# line_sensor.net
KiCad netlist of a schematic drawn in EAGLE
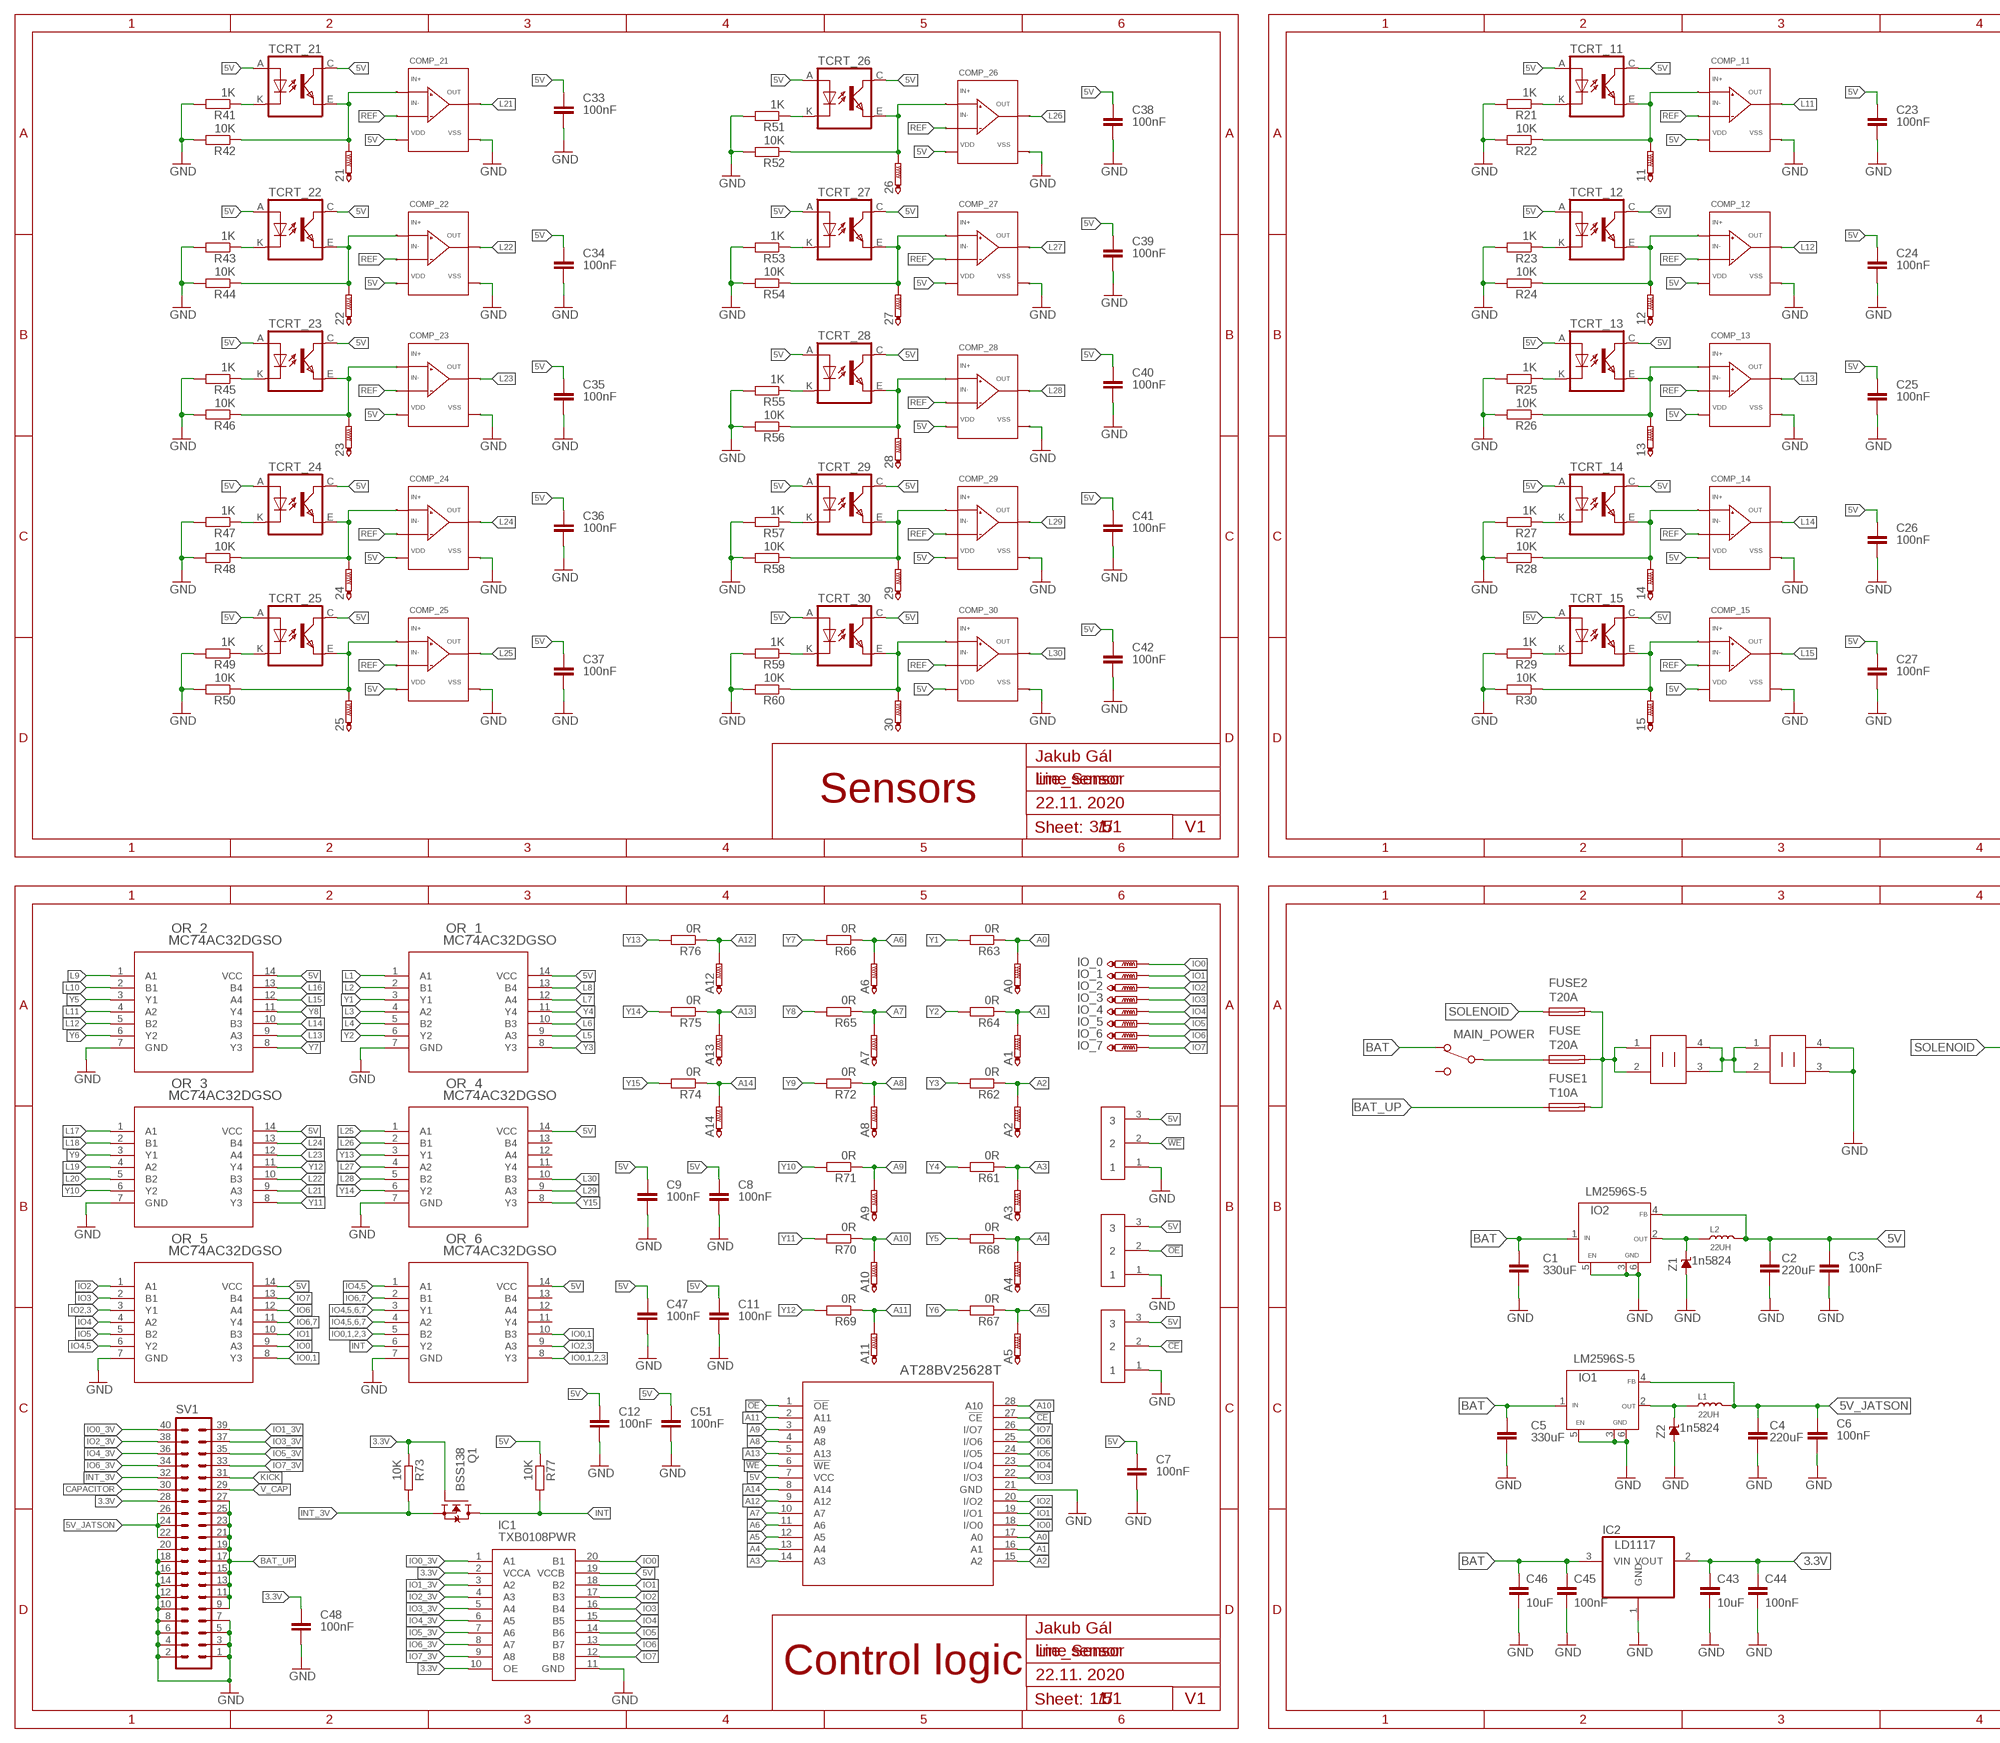
[diagram p0: schematic, sheet 1, part 1 of 2]
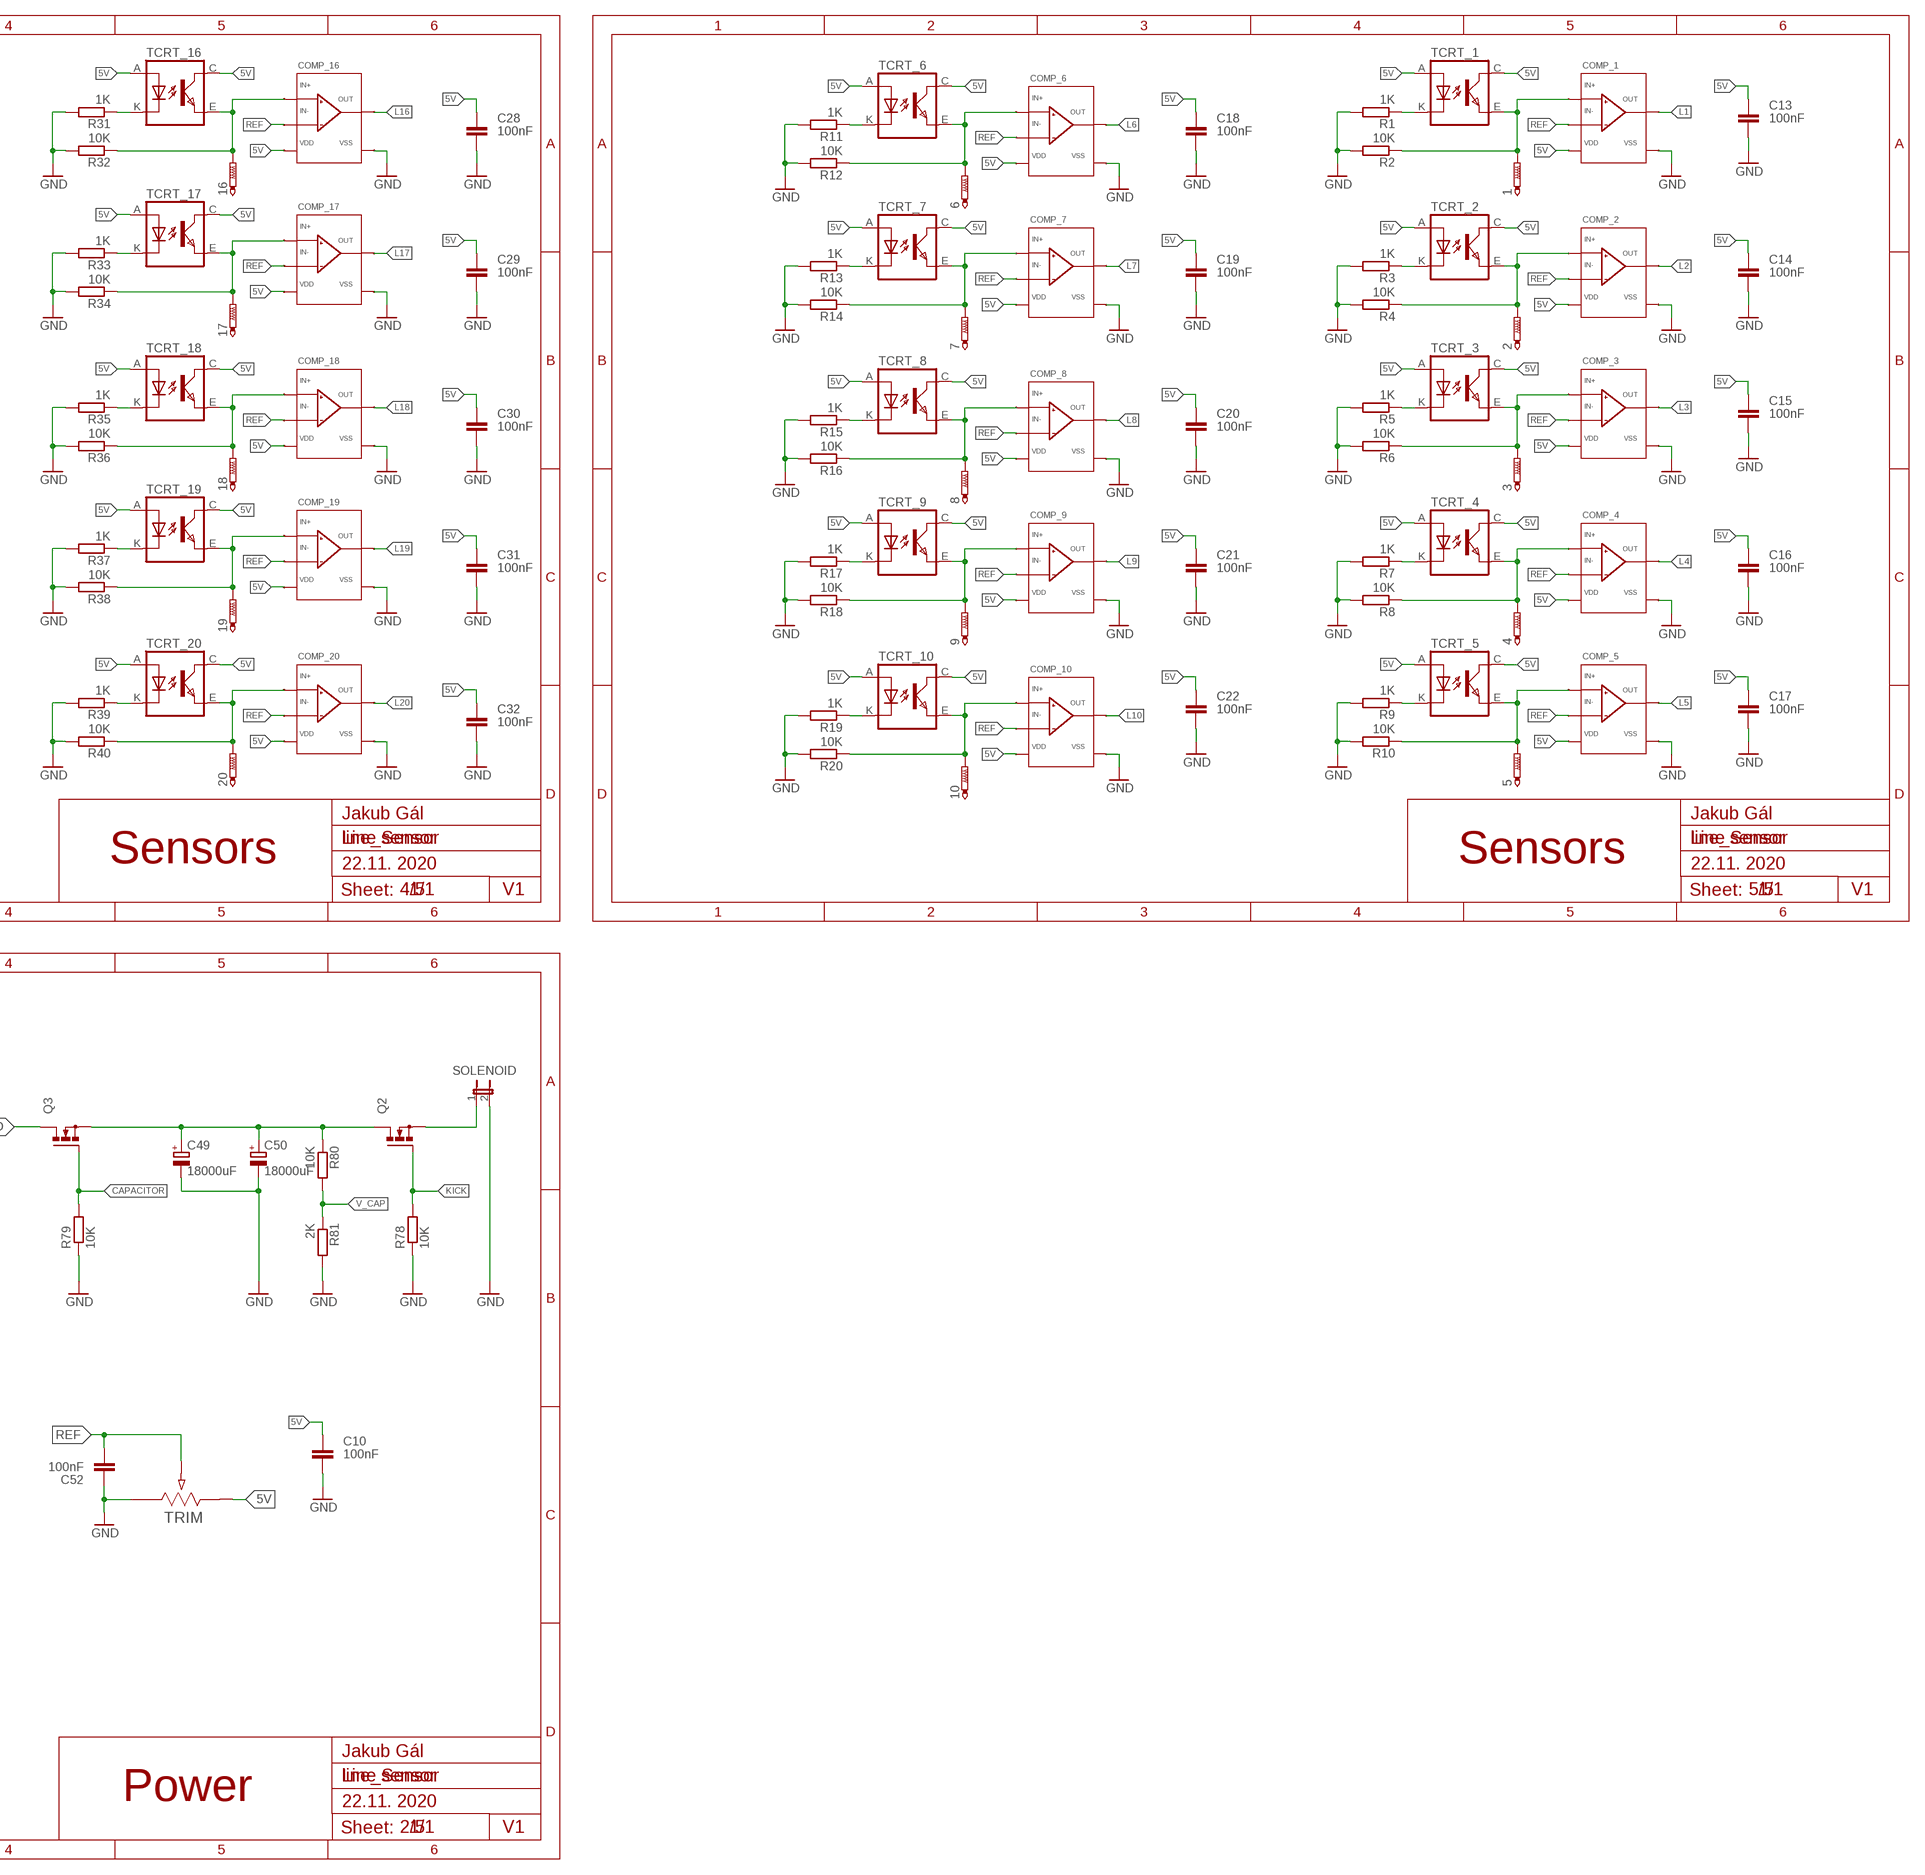
[diagram p1: schematic, sheet 1, part 2 of 2]

(export (version "E")
  (design (tool "Eeschema 10.0.6"))
  (components
    (comp (ref "!CE")
      (value "0603_S")
      (footprint "eagle-import:0603_S")
      (libsource (lib "eagle-import") (part "0603_S"))
    )
    (comp (ref "!OE")
      (value "0603_S")
      (footprint "eagle-import:0603_S")
      (libsource (lib "eagle-import") (part "0603_S"))
    )
    (comp (ref "!WE")
      (value "0603_S")
      (footprint "eagle-import:0603_S")
      (libsource (lib "eagle-import") (part "0603_S"))
    )
    (comp (ref "1")
      (value "PTR1TP20R")
      (footprint "eagle-import:TP20R")
      (libsource (lib "eagle-import") (part "PTR1TP20R"))
    )
    (comp (ref "2")
      (value "PTR1TP20R")
      (footprint "eagle-import:TP20R")
      (libsource (lib "eagle-import") (part "PTR1TP20R"))
    )
    (comp (ref "3")
      (value "PTR1TP20R")
      (footprint "eagle-import:TP20R")
      (libsource (lib "eagle-import") (part "PTR1TP20R"))
    )
    (comp (ref "4")
      (value "PTR1TP20R")
      (footprint "eagle-import:TP20R")
      (libsource (lib "eagle-import") (part "PTR1TP20R"))
    )
    (comp (ref "5")
      (value "PTR1TP20R")
      (footprint "eagle-import:TP20R")
      (libsource (lib "eagle-import") (part "PTR1TP20R"))
    )
    (comp (ref "6")
      (value "PTR1TP20R")
      (footprint "eagle-import:TP20R")
      (libsource (lib "eagle-import") (part "PTR1TP20R"))
    )
    (comp (ref "7")
      (value "PTR1TP20R")
      (footprint "eagle-import:TP20R")
      (libsource (lib "eagle-import") (part "PTR1TP20R"))
    )
    (comp (ref "8")
      (value "PTR1TP20R")
      (footprint "eagle-import:TP20R")
      (libsource (lib "eagle-import") (part "PTR1TP20R"))
    )
    (comp (ref "9")
      (value "PTR1TP20R")
      (footprint "eagle-import:TP20R")
      (libsource (lib "eagle-import") (part "PTR1TP20R"))
    )
    (comp (ref "10")
      (value "PTR1TP20R")
      (footprint "eagle-import:TP20R")
      (libsource (lib "eagle-import") (part "PTR1TP20R"))
    )
    (comp (ref "11")
      (value "PTR1TP20R")
      (footprint "eagle-import:TP20R")
      (libsource (lib "eagle-import") (part "PTR1TP20R"))
    )
    (comp (ref "12")
      (value "PTR1TP20R")
      (footprint "eagle-import:TP20R")
      (libsource (lib "eagle-import") (part "PTR1TP20R"))
    )
    (comp (ref "13")
      (value "PTR1TP20R")
      (footprint "eagle-import:TP20R")
      (libsource (lib "eagle-import") (part "PTR1TP20R"))
    )
    (comp (ref "14")
      (value "PTR1TP20R")
      (footprint "eagle-import:TP20R")
      (libsource (lib "eagle-import") (part "PTR1TP20R"))
    )
    (comp (ref "15")
      (value "PTR1TP20R")
      (footprint "eagle-import:TP20R")
      (libsource (lib "eagle-import") (part "PTR1TP20R"))
    )
    (comp (ref "16")
      (value "PTR1TP20R")
      (footprint "eagle-import:TP20R")
      (libsource (lib "eagle-import") (part "PTR1TP20R"))
    )
    (comp (ref "17")
      (value "PTR1TP20R")
      (footprint "eagle-import:TP20R")
      (libsource (lib "eagle-import") (part "PTR1TP20R"))
    )
    (comp (ref "18")
      (value "PTR1TP20R")
      (footprint "eagle-import:TP20R")
      (libsource (lib "eagle-import") (part "PTR1TP20R"))
    )
    (comp (ref "19")
      (value "PTR1TP20R")
      (footprint "eagle-import:TP20R")
      (libsource (lib "eagle-import") (part "PTR1TP20R"))
    )
    (comp (ref "20")
      (value "PTR1TP20R")
      (footprint "eagle-import:TP20R")
      (libsource (lib "eagle-import") (part "PTR1TP20R"))
    )
    (comp (ref "21")
      (value "PTR1TP20R")
      (footprint "eagle-import:TP20R")
      (libsource (lib "eagle-import") (part "PTR1TP20R"))
    )
    (comp (ref "22")
      (value "PTR1TP20R")
      (footprint "eagle-import:TP20R")
      (libsource (lib "eagle-import") (part "PTR1TP20R"))
    )
    (comp (ref "23")
      (value "PTR1TP20R")
      (footprint "eagle-import:TP20R")
      (libsource (lib "eagle-import") (part "PTR1TP20R"))
    )
    (comp (ref "24")
      (value "PTR1TP20R")
      (footprint "eagle-import:TP20R")
      (libsource (lib "eagle-import") (part "PTR1TP20R"))
    )
    (comp (ref "25")
      (value "PTR1TP20R")
      (footprint "eagle-import:TP20R")
      (libsource (lib "eagle-import") (part "PTR1TP20R"))
    )
    (comp (ref "26")
      (value "PTR1TP20R")
      (footprint "eagle-import:TP20R")
      (libsource (lib "eagle-import") (part "PTR1TP20R"))
    )
    (comp (ref "27")
      (value "PTR1TP20R")
      (footprint "eagle-import:TP20R")
      (libsource (lib "eagle-import") (part "PTR1TP20R"))
    )
    (comp (ref "28")
      (value "PTR1TP20R")
      (footprint "eagle-import:TP20R")
      (libsource (lib "eagle-import") (part "PTR1TP20R"))
    )
    (comp (ref "29")
      (value "PTR1TP20R")
      (footprint "eagle-import:TP20R")
      (libsource (lib "eagle-import") (part "PTR1TP20R"))
    )
    (comp (ref "30")
      (value "PTR1TP20R")
      (footprint "eagle-import:TP20R")
      (libsource (lib "eagle-import") (part "PTR1TP20R"))
    )
    (comp (ref "A0")
      (value "PTR1TP20R")
      (footprint "eagle-import:TP20R")
      (libsource (lib "eagle-import") (part "PTR1TP20R"))
    )
    (comp (ref "A1")
      (value "PTR1TP20R")
      (footprint "eagle-import:TP20R")
      (libsource (lib "eagle-import") (part "PTR1TP20R"))
    )
    (comp (ref "A2")
      (value "PTR1TP20R")
      (footprint "eagle-import:TP20R")
      (libsource (lib "eagle-import") (part "PTR1TP20R"))
    )
    (comp (ref "A3")
      (value "PTR1TP20R")
      (footprint "eagle-import:TP20R")
      (libsource (lib "eagle-import") (part "PTR1TP20R"))
    )
    (comp (ref "A4")
      (value "PTR1TP20R")
      (footprint "eagle-import:TP20R")
      (libsource (lib "eagle-import") (part "PTR1TP20R"))
    )
    (comp (ref "A5")
      (value "PTR1TP20R")
      (footprint "eagle-import:TP20R")
      (libsource (lib "eagle-import") (part "PTR1TP20R"))
    )
    (comp (ref "A6")
      (value "PTR1TP20R")
      (footprint "eagle-import:TP20R")
      (libsource (lib "eagle-import") (part "PTR1TP20R"))
    )
    (comp (ref "A7")
      (value "PTR1TP20R")
      (footprint "eagle-import:TP20R")
      (libsource (lib "eagle-import") (part "PTR1TP20R"))
    )
    (comp (ref "A8")
      (value "PTR1TP20R")
      (footprint "eagle-import:TP20R")
      (libsource (lib "eagle-import") (part "PTR1TP20R"))
    )
    (comp (ref "A9")
      (value "PTR1TP20R")
      (footprint "eagle-import:TP20R")
      (libsource (lib "eagle-import") (part "PTR1TP20R"))
    )
    (comp (ref "A10")
      (value "PTR1TP20R")
      (footprint "eagle-import:TP20R")
      (libsource (lib "eagle-import") (part "PTR1TP20R"))
    )
    (comp (ref "A11")
      (value "PTR1TP20R")
      (footprint "eagle-import:TP20R")
      (libsource (lib "eagle-import") (part "PTR1TP20R"))
    )
    (comp (ref "A12")
      (value "PTR1TP20R")
      (footprint "eagle-import:TP20R")
      (libsource (lib "eagle-import") (part "PTR1TP20R"))
    )
    (comp (ref "A13")
      (value "PTR1TP20R")
      (footprint "eagle-import:TP20R")
      (libsource (lib "eagle-import") (part "PTR1TP20R"))
    )
    (comp (ref "A14")
      (value "PTR1TP20R")
      (footprint "eagle-import:TP20R")
      (libsource (lib "eagle-import") (part "PTR1TP20R"))
    )
    (comp (ref "AT28BV25628T")
      (value "AT28BV25628T_ATM-M")
      (footprint "eagle-import:28T_ATM-M")
      (fields (field (name "MANUFACTURER_PART_NUMBER") "AT28BV256-20TU"))
      (libsource (lib "eagle-import") (part "AT28BV25628T_ATM-M"))
    )
    (comp (ref "C1")
      (value "330uF")
      (footprint "eagle-import:CAPM7343X310")
      (libsource (lib "eagle-import") (part "CTANTALUM-2917(7343-METRIC)_"))
    )
    (comp (ref "C2")
      (value "220uF")
      (footprint "eagle-import:CAPM7343X310")
      (libsource (lib "eagle-import") (part "CTANTALUM-2917(7343-METRIC)_"))
    )
    (comp (ref "C3")
      (value "100nF")
      (footprint "eagle-import:C0603")
      (libsource (lib "eagle-import") (part "C-EUC0603"))
    )
    (comp (ref "C4")
      (value "220uF")
      (footprint "eagle-import:CAPM7343X310")
      (libsource (lib "eagle-import") (part "CTANTALUM-2917(7343-METRIC)_"))
    )
    (comp (ref "C5")
      (value "330uF")
      (footprint "eagle-import:CAPM7343X310")
      (libsource (lib "eagle-import") (part "CTANTALUM-2917(7343-METRIC)_"))
    )
    (comp (ref "C6")
      (value "100nF")
      (footprint "eagle-import:C0603")
      (libsource (lib "eagle-import") (part "C-EUC0603"))
    )
    (comp (ref "C7")
      (value "100nF")
      (footprint "eagle-import:C0603")
      (libsource (lib "eagle-import") (part "C-EUC0603"))
    )
    (comp (ref "C8")
      (value "100nF")
      (footprint "eagle-import:C0603")
      (libsource (lib "eagle-import") (part "C-EUC0603"))
    )
    (comp (ref "C9")
      (value "100nF")
      (footprint "eagle-import:C0603")
      (libsource (lib "eagle-import") (part "C-EUC0603"))
    )
    (comp (ref "C10")
      (value "100nF")
      (footprint "eagle-import:C0603")
      (libsource (lib "eagle-import") (part "C-EUC0603"))
    )
    (comp (ref "C11")
      (value "100nF")
      (footprint "eagle-import:C0603")
      (libsource (lib "eagle-import") (part "C-EUC0603"))
    )
    (comp (ref "C12")
      (value "100nF")
      (footprint "eagle-import:C0603")
      (libsource (lib "eagle-import") (part "C-EUC0603"))
    )
    (comp (ref "C13")
      (value "100nF")
      (footprint "eagle-import:C0603")
      (libsource (lib "eagle-import") (part "C-EUC0603"))
    )
    (comp (ref "C14")
      (value "100nF")
      (footprint "eagle-import:C0603")
      (libsource (lib "eagle-import") (part "C-EUC0603"))
    )
    (comp (ref "C15")
      (value "100nF")
      (footprint "eagle-import:C0603")
      (libsource (lib "eagle-import") (part "C-EUC0603"))
    )
    (comp (ref "C16")
      (value "100nF")
      (footprint "eagle-import:C0603")
      (libsource (lib "eagle-import") (part "C-EUC0603"))
    )
    (comp (ref "C17")
      (value "100nF")
      (footprint "eagle-import:C0603")
      (libsource (lib "eagle-import") (part "C-EUC0603"))
    )
    (comp (ref "C18")
      (value "100nF")
      (footprint "eagle-import:C0603")
      (libsource (lib "eagle-import") (part "C-EUC0603"))
    )
    (comp (ref "C19")
      (value "100nF")
      (footprint "eagle-import:C0603")
      (libsource (lib "eagle-import") (part "C-EUC0603"))
    )
    (comp (ref "C20")
      (value "100nF")
      (footprint "eagle-import:C0603")
      (libsource (lib "eagle-import") (part "C-EUC0603"))
    )
    (comp (ref "C21")
      (value "100nF")
      (footprint "eagle-import:C0603")
      (libsource (lib "eagle-import") (part "C-EUC0603"))
    )
    (comp (ref "C22")
      (value "100nF")
      (footprint "eagle-import:C0603")
      (libsource (lib "eagle-import") (part "C-EUC0603"))
    )
    (comp (ref "C23")
      (value "100nF")
      (footprint "eagle-import:C0603")
      (libsource (lib "eagle-import") (part "C-EUC0603"))
    )
    (comp (ref "C24")
      (value "100nF")
      (footprint "eagle-import:C0603")
      (libsource (lib "eagle-import") (part "C-EUC0603"))
    )
    (comp (ref "C25")
      (value "100nF")
      (footprint "eagle-import:C0603")
      (libsource (lib "eagle-import") (part "C-EUC0603"))
    )
    (comp (ref "C26")
      (value "100nF")
      (footprint "eagle-import:C0603")
      (libsource (lib "eagle-import") (part "C-EUC0603"))
    )
    (comp (ref "C27")
      (value "100nF")
      (footprint "eagle-import:C0603")
      (libsource (lib "eagle-import") (part "C-EUC0603"))
    )
    (comp (ref "C28")
      (value "100nF")
      (footprint "eagle-import:C0603")
      (libsource (lib "eagle-import") (part "C-EUC0603"))
    )
    (comp (ref "C29")
      (value "100nF")
      (footprint "eagle-import:C0603")
      (libsource (lib "eagle-import") (part "C-EUC0603"))
    )
    (comp (ref "C30")
      (value "100nF")
      (footprint "eagle-import:C0603")
      (libsource (lib "eagle-import") (part "C-EUC0603"))
    )
    (comp (ref "C31")
      (value "100nF")
      (footprint "eagle-import:C0603")
      (libsource (lib "eagle-import") (part "C-EUC0603"))
    )
    (comp (ref "C32")
      (value "100nF")
      (footprint "eagle-import:C0603")
      (libsource (lib "eagle-import") (part "C-EUC0603"))
    )
    (comp (ref "C33")
      (value "100nF")
      (footprint "eagle-import:C0603")
      (libsource (lib "eagle-import") (part "C-EUC0603"))
    )
    (comp (ref "C34")
      (value "100nF")
      (footprint "eagle-import:C0603")
      (libsource (lib "eagle-import") (part "C-EUC0603"))
    )
    (comp (ref "C35")
      (value "100nF")
      (footprint "eagle-import:C0603")
      (libsource (lib "eagle-import") (part "C-EUC0603"))
    )
    (comp (ref "C36")
      (value "100nF")
      (footprint "eagle-import:C0603")
      (libsource (lib "eagle-import") (part "C-EUC0603"))
    )
    (comp (ref "C37")
      (value "100nF")
      (footprint "eagle-import:C0603")
      (libsource (lib "eagle-import") (part "C-EUC0603"))
    )
    (comp (ref "C38")
      (value "100nF")
      (footprint "eagle-import:C0603")
      (libsource (lib "eagle-import") (part "C-EUC0603"))
    )
    (comp (ref "C39")
      (value "100nF")
      (footprint "eagle-import:C0603")
      (libsource (lib "eagle-import") (part "C-EUC0603"))
    )
    (comp (ref "C40")
      (value "100nF")
      (footprint "eagle-import:C0603")
      (libsource (lib "eagle-import") (part "C-EUC0603"))
    )
    (comp (ref "C41")
      (value "100nF")
      (footprint "eagle-import:C0603")
      (libsource (lib "eagle-import") (part "C-EUC0603"))
    )
    (comp (ref "C42")
      (value "100nF")
      (footprint "eagle-import:C0603")
      (libsource (lib "eagle-import") (part "C-EUC0603"))
    )
    (comp (ref "C43")
      (value "10uF")
      (footprint "eagle-import:C0603")
      (libsource (lib "eagle-import") (part "C-EUC0603"))
    )
    (comp (ref "C44")
      (value "100nF")
      (footprint "eagle-import:C0603")
      (libsource (lib "eagle-import") (part "C-EUC0603"))
    )
    (comp (ref "C45")
      (value "100nF")
      (footprint "eagle-import:C0603")
      (libsource (lib "eagle-import") (part "C-EUC0603"))
    )
    (comp (ref "C46")
      (value "10uF")
      (footprint "eagle-import:C0603")
      (libsource (lib "eagle-import") (part "C-EUC0603"))
    )
    (comp (ref "C47")
      (value "100nF")
      (footprint "eagle-import:C0603")
      (libsource (lib "eagle-import") (part "C-EUC0603"))
    )
    (comp (ref "C48")
      (value "100nF")
      (footprint "eagle-import:C0603")
      (libsource (lib "eagle-import") (part "C-EUC0603"))
    )
    (comp (ref "C49")
      (value "18000uF")
      (footprint "eagle-import:EB30D")
      (libsource (lib "eagle-import") (part "CPOL-EUE10-30"))
    )
    (comp (ref "C50")
      (value "18000uF")
      (footprint "eagle-import:EB30D")
      (libsource (lib "eagle-import") (part "CPOL-EUE10-30"))
    )
    (comp (ref "C51")
      (value "100nF")
      (footprint "eagle-import:C0603")
      (libsource (lib "eagle-import") (part "C-EUC0603"))
    )
    (comp (ref "C52")
      (value "100nF")
      (footprint "eagle-import:C0603")
      (libsource (lib "eagle-import") (part "C-EUC0603"))
    )
    (comp (ref "COMP_1")
      (value "TC75S56FUTE85LF")
      (footprint "eagle-import:SOT-353___(USV)_TOS")
      (libsource (lib "eagle-import") (part "TC75S56FUTE85LF"))
    )
    (comp (ref "COMP_2")
      (value "TC75S56FUTE85LF")
      (footprint "eagle-import:SOT-353___(USV)_TOS")
      (libsource (lib "eagle-import") (part "TC75S56FUTE85LF"))
    )
    (comp (ref "COMP_3")
      (value "TC75S56FUTE85LF")
      (footprint "eagle-import:SOT-353___(USV)_TOS")
      (libsource (lib "eagle-import") (part "TC75S56FUTE85LF"))
    )
    (comp (ref "COMP_4")
      (value "TC75S56FUTE85LF")
      (footprint "eagle-import:SOT-353___(USV)_TOS")
      (libsource (lib "eagle-import") (part "TC75S56FUTE85LF"))
    )
    (comp (ref "COMP_5")
      (value "TC75S56FUTE85LF")
      (footprint "eagle-import:SOT-353___(USV)_TOS")
      (libsource (lib "eagle-import") (part "TC75S56FUTE85LF"))
    )
    (comp (ref "COMP_6")
      (value "TC75S56FUTE85LF")
      (footprint "eagle-import:SOT-353___(USV)_TOS")
      (libsource (lib "eagle-import") (part "TC75S56FUTE85LF"))
    )
    (comp (ref "COMP_7")
      (value "TC75S56FUTE85LF")
      (footprint "eagle-import:SOT-353___(USV)_TOS")
      (libsource (lib "eagle-import") (part "TC75S56FUTE85LF"))
    )
    (comp (ref "COMP_8")
      (value "TC75S56FUTE85LF")
      (footprint "eagle-import:SOT-353___(USV)_TOS")
      (libsource (lib "eagle-import") (part "TC75S56FUTE85LF"))
    )
    (comp (ref "COMP_9")
      (value "TC75S56FUTE85LF")
      (footprint "eagle-import:SOT-353___(USV)_TOS")
      (libsource (lib "eagle-import") (part "TC75S56FUTE85LF"))
    )
    (comp (ref "COMP_10")
      (value "TC75S56FUTE85LF")
      (footprint "eagle-import:SOT-353___(USV)_TOS")
      (libsource (lib "eagle-import") (part "TC75S56FUTE85LF"))
    )
    (comp (ref "COMP_11")
      (value "TC75S56FUTE85LF")
      (footprint "eagle-import:SOT-353___(USV)_TOS")
      (libsource (lib "eagle-import") (part "TC75S56FUTE85LF"))
    )
    (comp (ref "COMP_12")
      (value "TC75S56FUTE85LF")
      (footprint "eagle-import:SOT-353___(USV)_TOS")
      (libsource (lib "eagle-import") (part "TC75S56FUTE85LF"))
    )
    (comp (ref "COMP_13")
      (value "TC75S56FUTE85LF")
      (footprint "eagle-import:SOT-353___(USV)_TOS")
      (libsource (lib "eagle-import") (part "TC75S56FUTE85LF"))
    )
    (comp (ref "COMP_14")
      (value "TC75S56FUTE85LF")
      (footprint "eagle-import:SOT-353___(USV)_TOS")
      (libsource (lib "eagle-import") (part "TC75S56FUTE85LF"))
    )
    (comp (ref "COMP_15")
      (value "TC75S56FUTE85LF")
      (footprint "eagle-import:SOT-353___(USV)_TOS")
      (libsource (lib "eagle-import") (part "TC75S56FUTE85LF"))
    )
    (comp (ref "COMP_16")
      (value "TC75S56FUTE85LF")
      (footprint "eagle-import:SOT-353___(USV)_TOS")
      (libsource (lib "eagle-import") (part "TC75S56FUTE85LF"))
    )
    (comp (ref "COMP_17")
      (value "TC75S56FUTE85LF")
      (footprint "eagle-import:SOT-353___(USV)_TOS")
      (libsource (lib "eagle-import") (part "TC75S56FUTE85LF"))
    )
    (comp (ref "COMP_18")
      (value "TC75S56FUTE85LF")
      (footprint "eagle-import:SOT-353___(USV)_TOS")
      (libsource (lib "eagle-import") (part "TC75S56FUTE85LF"))
    )
    (comp (ref "COMP_19")
      (value "TC75S56FUTE85LF")
      (footprint "eagle-import:SOT-353___(USV)_TOS")
      (libsource (lib "eagle-import") (part "TC75S56FUTE85LF"))
    )
    (comp (ref "COMP_20")
      (value "TC75S56FUTE85LF")
      (footprint "eagle-import:SOT-353___(USV)_TOS")
      (libsource (lib "eagle-import") (part "TC75S56FUTE85LF"))
    )
    (comp (ref "COMP_21")
      (value "TC75S56FUTE85LF")
      (footprint "eagle-import:SOT-353___(USV)_TOS")
      (libsource (lib "eagle-import") (part "TC75S56FUTE85LF"))
    )
    (comp (ref "COMP_22")
      (value "TC75S56FUTE85LF")
      (footprint "eagle-import:SOT-353___(USV)_TOS")
      (libsource (lib "eagle-import") (part "TC75S56FUTE85LF"))
    )
    (comp (ref "COMP_23")
      (value "TC75S56FUTE85LF")
      (footprint "eagle-import:SOT-353___(USV)_TOS")
      (libsource (lib "eagle-import") (part "TC75S56FUTE85LF"))
    )
    (comp (ref "COMP_24")
      (value "TC75S56FUTE85LF")
      (footprint "eagle-import:SOT-353___(USV)_TOS")
      (libsource (lib "eagle-import") (part "TC75S56FUTE85LF"))
    )
    (comp (ref "COMP_25")
      (value "TC75S56FUTE85LF")
      (footprint "eagle-import:SOT-353___(USV)_TOS")
      (libsource (lib "eagle-import") (part "TC75S56FUTE85LF"))
    )
    (comp (ref "COMP_26")
      (value "TC75S56FUTE85LF")
      (footprint "eagle-import:SOT-353___(USV)_TOS")
      (libsource (lib "eagle-import") (part "TC75S56FUTE85LF"))
    )
    (comp (ref "COMP_27")
      (value "TC75S56FUTE85LF")
      (footprint "eagle-import:SOT-353___(USV)_TOS")
      (libsource (lib "eagle-import") (part "TC75S56FUTE85LF"))
    )
    (comp (ref "COMP_28")
      (value "TC75S56FUTE85LF")
      (footprint "eagle-import:SOT-353___(USV)_TOS")
      (libsource (lib "eagle-import") (part "TC75S56FUTE85LF"))
    )
    (comp (ref "COMP_29")
      (value "TC75S56FUTE85LF")
      (footprint "eagle-import:SOT-353___(USV)_TOS")
      (libsource (lib "eagle-import") (part "TC75S56FUTE85LF"))
    )
    (comp (ref "COMP_30")
      (value "TC75S56FUTE85LF")
      (footprint "eagle-import:SOT-353___(USV)_TOS")
      (libsource (lib "eagle-import") (part "TC75S56FUTE85LF"))
    )
    (comp (ref "FUSE")
      (value "T20A")
      (footprint "eagle-import:SH22,5A")
      (libsource (lib "eagle-import") (part "POISTKA2A"))
    )
    (comp (ref "FUSE1")
      (value "T10A")
      (footprint "eagle-import:SH22,5A")
      (libsource (lib "eagle-import") (part "POISTKA2A"))
    )
    (comp (ref "FUSE2")
      (value "T20A")
      (footprint "eagle-import:SH22,5A")
      (libsource (lib "eagle-import") (part "POISTKA2A"))
    )
    (comp (ref "IC1")
      (value "TXB0108PWR")
      (footprint "eagle-import:SOP65P640X120-20N")
      (fields (field (name "MOUSER_PART_NUMBER") "595-TXB0108PWR"))
      (libsource (lib "eagle-import") (part "TXB0108PWR"))
    )
    (comp (ref "IC2")
      (value "LD1117")
      (footprint "eagle-import:SOT223")
      (fields (field (name "MF") "TEXAS INSTRUMENTS") (field (name "MPN") "REG1117FAKTTT"))
      (libsource (lib "eagle-import") (part "LD1117"))
    )
    (comp (ref "IO1")
      (value "LM2596S-5")
      (footprint "eagle-import:TO263-5")
      (libsource (lib "eagle-import") (part "LM2596S"))
    )
    (comp (ref "IO2")
      (value "LM2596S-5")
      (footprint "eagle-import:TO263-5")
      (libsource (lib "eagle-import") (part "LM2596S"))
    )
    (comp (ref "IO_0")
      (value "PTR1TP20R")
      (footprint "eagle-import:TP20R")
      (libsource (lib "eagle-import") (part "PTR1TP20R"))
    )
    (comp (ref "IO_1")
      (value "PTR1TP20R")
      (footprint "eagle-import:TP20R")
      (libsource (lib "eagle-import") (part "PTR1TP20R"))
    )
    (comp (ref "IO_2")
      (value "PTR1TP20R")
      (footprint "eagle-import:TP20R")
      (libsource (lib "eagle-import") (part "PTR1TP20R"))
    )
    (comp (ref "IO_3")
      (value "PTR1TP20R")
      (footprint "eagle-import:TP20R")
      (libsource (lib "eagle-import") (part "PTR1TP20R"))
    )
    (comp (ref "IO_4")
      (value "PTR1TP20R")
      (footprint "eagle-import:TP20R")
      (libsource (lib "eagle-import") (part "PTR1TP20R"))
    )
    (comp (ref "IO_5")
      (value "PTR1TP20R")
      (footprint "eagle-import:TP20R")
      (libsource (lib "eagle-import") (part "PTR1TP20R"))
    )
    (comp (ref "IO_6")
      (value "PTR1TP20R")
      (footprint "eagle-import:TP20R")
      (libsource (lib "eagle-import") (part "PTR1TP20R"))
    )
    (comp (ref "IO_7")
      (value "PTR1TP20R")
      (footprint "eagle-import:TP20R")
      (libsource (lib "eagle-import") (part "PTR1TP20R"))
    )
    (comp (ref "L1")
      (value "22UH")
      (footprint "eagle-import:INDUCTOR_L0630")
      (libsource (lib "eagle-import") (part "INDUCTOR/FERRITE-BEAD0630"))
    )
    (comp (ref "L2")
      (value "22UH")
      (footprint "eagle-import:INDUCTOR_L0630")
      (libsource (lib "eagle-import") (part "INDUCTOR/FERRITE-BEAD0630"))
    )
    (comp (ref "MAIN_POWER")
      (value "PREP-1PB")
      (footprint "eagle-import:P-B069B")
      (libsource (lib "eagle-import") (part "PREP-1PB"))
    )
    (comp (ref "OR_1")
      (value "MC74AC32DGSO")
      (footprint "eagle-import:SOIC-14_NB_ONS-M")
      (fields
        (field (name "MANUFACTURER_PART_NUMBER") "MC74VHC32DR2G")
        (field (name "COPYRIGHT") "Copyright (C) 2016 Accelerated Designs. All rights reserved")
      )
      (libsource (lib "eagle-import") (part "MC74AC32DGSOIC-14_NB_ONS-M"))
    )
    (comp (ref "OR_2")
      (value "MC74AC32DGSO")
      (footprint "eagle-import:SOIC-14_NB_ONS-M")
      (fields
        (field (name "MANUFACTURER_PART_NUMBER") "MC74VHC32DR2G")
        (field (name "COPYRIGHT") "Copyright (C) 2016 Accelerated Designs. All rights reserved")
      )
      (libsource (lib "eagle-import") (part "MC74AC32DGSOIC-14_NB_ONS-M"))
    )
    (comp (ref "OR_3")
      (value "MC74AC32DGSO")
      (footprint "eagle-import:SOIC-14_NB_ONS-M")
      (fields
        (field (name "MANUFACTURER_PART_NUMBER") "MC74VHC32DR2G")
        (field (name "COPYRIGHT") "Copyright (C) 2016 Accelerated Designs. All rights reserved")
      )
      (libsource (lib "eagle-import") (part "MC74AC32DGSOIC-14_NB_ONS-M"))
    )
    (comp (ref "OR_4")
      (value "MC74AC32DGSO")
      (footprint "eagle-import:SOIC-14_NB_ONS-M")
      (fields
        (field (name "MANUFACTURER_PART_NUMBER") "MC74VHC32DR2G")
        (field (name "COPYRIGHT") "Copyright (C) 2016 Accelerated Designs. All rights reserved")
      )
      (libsource (lib "eagle-import") (part "MC74AC32DGSOIC-14_NB_ONS-M"))
    )
    (comp (ref "OR_5")
      (value "MC74AC32DGSO")
      (footprint "eagle-import:SOIC-14_NB_ONS-M")
      (fields
        (field (name "MANUFACTURER_PART_NUMBER") "MC74VHC32DR2G")
        (field (name "COPYRIGHT") "Copyright (C) 2016 Accelerated Designs. All rights reserved")
      )
      (libsource (lib "eagle-import") (part "MC74AC32DGSOIC-14_NB_ONS-M"))
    )
    (comp (ref "OR_6")
      (value "MC74AC32DGSO")
      (footprint "eagle-import:SOIC-14_NB_ONS-M")
      (fields
        (field (name "MANUFACTURER_PART_NUMBER") "MC74VHC32DR2G")
        (field (name "COPYRIGHT") "Copyright (C) 2016 Accelerated Designs. All rights reserved")
      )
      (libsource (lib "eagle-import") (part "MC74AC32DGSOIC-14_NB_ONS-M"))
    )
    (comp (ref "Q1")
      (value "BSS138")
      (footprint "eagle-import:SOT23")
      (fields (field (name "MF") "Fairchild"))
      (libsource (lib "eagle-import") (part "BSS138"))
    )
    (comp (ref "Q2")
      (value "PMOSFET_NTO220BV")
      (footprint "eagle-import:TO220BV")
      (libsource (lib "eagle-import") (part "PMOSFET_NTO220BV"))
    )
    (comp (ref "Q3")
      (value "PMOSFET_NTO220BV")
      (footprint "eagle-import:TO220BV")
      (libsource (lib "eagle-import") (part "PMOSFET_NTO220BV"))
    )
    (comp (ref "R1")
      (value "1K")
      (footprint "eagle-import:R0603")
      (libsource (lib "eagle-import") (part "R-EU_R0603"))
    )
    (comp (ref "R2")
      (value "10K")
      (footprint "eagle-import:R0603")
      (libsource (lib "eagle-import") (part "R-EU_R0603"))
    )
    (comp (ref "R3")
      (value "1K")
      (footprint "eagle-import:R0603")
      (libsource (lib "eagle-import") (part "R-EU_R0603"))
    )
    (comp (ref "R4")
      (value "10K")
      (footprint "eagle-import:R0603")
      (libsource (lib "eagle-import") (part "R-EU_R0603"))
    )
    (comp (ref "R5")
      (value "1K")
      (footprint "eagle-import:R0603")
      (libsource (lib "eagle-import") (part "R-EU_R0603"))
    )
    (comp (ref "R6")
      (value "10K")
      (footprint "eagle-import:R0603")
      (libsource (lib "eagle-import") (part "R-EU_R0603"))
    )
    (comp (ref "R7")
      (value "1K")
      (footprint "eagle-import:R0603")
      (libsource (lib "eagle-import") (part "R-EU_R0603"))
    )
    (comp (ref "R8")
      (value "10K")
      (footprint "eagle-import:R0603")
      (libsource (lib "eagle-import") (part "R-EU_R0603"))
    )
    (comp (ref "R9")
      (value "1K")
      (footprint "eagle-import:R0603")
      (libsource (lib "eagle-import") (part "R-EU_R0603"))
    )
    (comp (ref "R10")
      (value "10K")
      (footprint "eagle-import:R0603")
      (libsource (lib "eagle-import") (part "R-EU_R0603"))
    )
    (comp (ref "R11")
      (value "1K")
      (footprint "eagle-import:R0603")
      (libsource (lib "eagle-import") (part "R-EU_R0603"))
    )
    (comp (ref "R12")
      (value "10K")
      (footprint "eagle-import:R0603")
      (libsource (lib "eagle-import") (part "R-EU_R0603"))
    )
    (comp (ref "R13")
      (value "1K")
      (footprint "eagle-import:R0603")
      (libsource (lib "eagle-import") (part "R-EU_R0603"))
    )
    (comp (ref "R14")
      (value "10K")
      (footprint "eagle-import:R0603")
      (libsource (lib "eagle-import") (part "R-EU_R0603"))
    )
    (comp (ref "R15")
      (value "1K")
      (footprint "eagle-import:R0603")
      (libsource (lib "eagle-import") (part "R-EU_R0603"))
    )
    (comp (ref "R16")
      (value "10K")
      (footprint "eagle-import:R0603")
      (libsource (lib "eagle-import") (part "R-EU_R0603"))
    )
    (comp (ref "R17")
      (value "1K")
      (footprint "eagle-import:R0603")
      (libsource (lib "eagle-import") (part "R-EU_R0603"))
    )
    (comp (ref "R18")
      (value "10K")
      (footprint "eagle-import:R0603")
      (libsource (lib "eagle-import") (part "R-EU_R0603"))
    )
    (comp (ref "R19")
      (value "1K")
      (footprint "eagle-import:R0603")
      (libsource (lib "eagle-import") (part "R-EU_R0603"))
    )
    (comp (ref "R20")
      (value "10K")
      (footprint "eagle-import:R0603")
      (libsource (lib "eagle-import") (part "R-EU_R0603"))
    )
    (comp (ref "R21")
      (value "1K")
      (footprint "eagle-import:R0603")
      (libsource (lib "eagle-import") (part "R-EU_R0603"))
    )
    (comp (ref "R22")
      (value "10K")
      (footprint "eagle-import:R0603")
      (libsource (lib "eagle-import") (part "R-EU_R0603"))
    )
    (comp (ref "R23")
      (value "1K")
      (footprint "eagle-import:R0603")
      (libsource (lib "eagle-import") (part "R-EU_R0603"))
    )
    (comp (ref "R24")
      (value "10K")
      (footprint "eagle-import:R0603")
      (libsource (lib "eagle-import") (part "R-EU_R0603"))
    )
    (comp (ref "R25")
      (value "1K")
      (footprint "eagle-import:R0603")
      (libsource (lib "eagle-import") (part "R-EU_R0603"))
    )
    (comp (ref "R26")
      (value "10K")
      (footprint "eagle-import:R0603")
      (libsource (lib "eagle-import") (part "R-EU_R0603"))
    )
    (comp (ref "R27")
      (value "1K")
      (footprint "eagle-import:R0603")
      (libsource (lib "eagle-import") (part "R-EU_R0603"))
    )
    (comp (ref "R28")
      (value "10K")
      (footprint "eagle-import:R0603")
      (libsource (lib "eagle-import") (part "R-EU_R0603"))
    )
    (comp (ref "R29")
      (value "1K")
      (footprint "eagle-import:R0603")
      (libsource (lib "eagle-import") (part "R-EU_R0603"))
    )
    (comp (ref "R30")
      (value "10K")
      (footprint "eagle-import:R0603")
      (libsource (lib "eagle-import") (part "R-EU_R0603"))
    )
    (comp (ref "R31")
      (value "1K")
      (footprint "eagle-import:R0603")
      (libsource (lib "eagle-import") (part "R-EU_R0603"))
    )
    (comp (ref "R32")
      (value "10K")
      (footprint "eagle-import:R0603")
      (libsource (lib "eagle-import") (part "R-EU_R0603"))
    )
    (comp (ref "R33")
      (value "1K")
      (footprint "eagle-import:R0603")
      (libsource (lib "eagle-import") (part "R-EU_R0603"))
    )
    (comp (ref "R34")
      (value "10K")
      (footprint "eagle-import:R0603")
      (libsource (lib "eagle-import") (part "R-EU_R0603"))
    )
    (comp (ref "R35")
      (value "1K")
      (footprint "eagle-import:R0603")
      (libsource (lib "eagle-import") (part "R-EU_R0603"))
    )
    (comp (ref "R36")
      (value "10K")
      (footprint "eagle-import:R0603")
      (libsource (lib "eagle-import") (part "R-EU_R0603"))
    )
    (comp (ref "R37")
      (value "1K")
      (footprint "eagle-import:R0603")
      (libsource (lib "eagle-import") (part "R-EU_R0603"))
    )
    (comp (ref "R38")
      (value "10K")
      (footprint "eagle-import:R0603")
      (libsource (lib "eagle-import") (part "R-EU_R0603"))
    )
    (comp (ref "R39")
      (value "1K")
      (footprint "eagle-import:R0603")
      (libsource (lib "eagle-import") (part "R-EU_R0603"))
    )
    (comp (ref "R40")
      (value "10K")
      (footprint "eagle-import:R0603")
      (libsource (lib "eagle-import") (part "R-EU_R0603"))
    )
    (comp (ref "R41")
      (value "1K")
      (footprint "eagle-import:R0603")
      (libsource (lib "eagle-import") (part "R-EU_R0603"))
    )
    (comp (ref "R42")
      (value "10K")
      (footprint "eagle-import:R0603")
      (libsource (lib "eagle-import") (part "R-EU_R0603"))
    )
    (comp (ref "R43")
      (value "1K")
      (footprint "eagle-import:R0603")
      (libsource (lib "eagle-import") (part "R-EU_R0603"))
    )
    (comp (ref "R44")
      (value "10K")
      (footprint "eagle-import:R0603")
      (libsource (lib "eagle-import") (part "R-EU_R0603"))
    )
    (comp (ref "R45")
      (value "1K")
      (footprint "eagle-import:R0603")
      (libsource (lib "eagle-import") (part "R-EU_R0603"))
    )
    (comp (ref "R46")
      (value "10K")
      (footprint "eagle-import:R0603")
      (libsource (lib "eagle-import") (part "R-EU_R0603"))
    )
    (comp (ref "R47")
      (value "1K")
      (footprint "eagle-import:R0603")
      (libsource (lib "eagle-import") (part "R-EU_R0603"))
    )
    (comp (ref "R48")
      (value "10K")
      (footprint "eagle-import:R0603")
      (libsource (lib "eagle-import") (part "R-EU_R0603"))
    )
    (comp (ref "R49")
      (value "1K")
      (footprint "eagle-import:R0603")
      (libsource (lib "eagle-import") (part "R-EU_R0603"))
    )
    (comp (ref "R50")
      (value "10K")
      (footprint "eagle-import:R0603")
      (libsource (lib "eagle-import") (part "R-EU_R0603"))
    )
    (comp (ref "R51")
      (value "1K")
      (footprint "eagle-import:R0603")
      (libsource (lib "eagle-import") (part "R-EU_R0603"))
    )
    (comp (ref "R52")
      (value "10K")
      (footprint "eagle-import:R0603")
      (libsource (lib "eagle-import") (part "R-EU_R0603"))
    )
    (comp (ref "R53")
      (value "1K")
      (footprint "eagle-import:R0603")
      (libsource (lib "eagle-import") (part "R-EU_R0603"))
    )
    (comp (ref "R54")
      (value "10K")
      (footprint "eagle-import:R0603")
      (libsource (lib "eagle-import") (part "R-EU_R0603"))
    )
    (comp (ref "R55")
      (value "1K")
      (footprint "eagle-import:R0603")
      (libsource (lib "eagle-import") (part "R-EU_R0603"))
    )
    (comp (ref "R56")
      (value "10K")
      (footprint "eagle-import:R0603")
      (libsource (lib "eagle-import") (part "R-EU_R0603"))
    )
    (comp (ref "R57")
      (value "1K")
      (footprint "eagle-import:R0603")
      (libsource (lib "eagle-import") (part "R-EU_R0603"))
    )
    (comp (ref "R58")
      (value "10K")
      (footprint "eagle-import:R0603")
      (libsource (lib "eagle-import") (part "R-EU_R0603"))
    )
    (comp (ref "R59")
      (value "1K")
      (footprint "eagle-import:R0603")
      (libsource (lib "eagle-import") (part "R-EU_R0603"))
    )
    (comp (ref "R60")
      (value "10K")
      (footprint "eagle-import:R0603")
      (libsource (lib "eagle-import") (part "R-EU_R0603"))
    )
    (comp (ref "R61")
      (value "0R")
      (footprint "eagle-import:R0603")
      (libsource (lib "eagle-import") (part "R-EU_R0603"))
    )
    (comp (ref "R62")
      (value "0R")
      (footprint "eagle-import:R0603")
      (libsource (lib "eagle-import") (part "R-EU_R0603"))
    )
    (comp (ref "R63")
      (value "0R")
      (footprint "eagle-import:R0603")
      (libsource (lib "eagle-import") (part "R-EU_R0603"))
    )
    (comp (ref "R64")
      (value "0R")
      (footprint "eagle-import:R0603")
      (libsource (lib "eagle-import") (part "R-EU_R0603"))
    )
    (comp (ref "R65")
      (value "0R")
      (footprint "eagle-import:R0603")
      (libsource (lib "eagle-import") (part "R-EU_R0603"))
    )
    (comp (ref "R66")
      (value "0R")
      (footprint "eagle-import:R0603")
      (libsource (lib "eagle-import") (part "R-EU_R0603"))
    )
    (comp (ref "R67")
      (value "0R")
      (footprint "eagle-import:R0603")
      (libsource (lib "eagle-import") (part "R-EU_R0603"))
    )
    (comp (ref "R68")
      (value "0R")
      (footprint "eagle-import:R0603")
      (libsource (lib "eagle-import") (part "R-EU_R0603"))
    )
    (comp (ref "R69")
      (value "0R")
      (footprint "eagle-import:R0603")
      (libsource (lib "eagle-import") (part "R-EU_R0603"))
    )
    (comp (ref "R70")
      (value "0R")
      (footprint "eagle-import:R0603")
      (libsource (lib "eagle-import") (part "R-EU_R0603"))
    )
    (comp (ref "R71")
      (value "0R")
      (footprint "eagle-import:R0603")
      (libsource (lib "eagle-import") (part "R-EU_R0603"))
    )
    (comp (ref "R72")
      (value "0R")
      (footprint "eagle-import:R0603")
      (libsource (lib "eagle-import") (part "R-EU_R0603"))
    )
    (comp (ref "R73")
      (value "10K")
      (footprint "eagle-import:R0603")
      (libsource (lib "eagle-import") (part "R-EU_R0603"))
    )
    (comp (ref "R74")
      (value "0R")
      (footprint "eagle-import:R0603")
      (libsource (lib "eagle-import") (part "R-EU_R0603"))
    )
    (comp (ref "R75")
      (value "0R")
      (footprint "eagle-import:R0603")
      (libsource (lib "eagle-import") (part "R-EU_R0603"))
    )
    (comp (ref "R76")
      (value "0R")
      (footprint "eagle-import:R0603")
      (libsource (lib "eagle-import") (part "R-EU_R0603"))
    )
    (comp (ref "R77")
      (value "10K")
      (footprint "eagle-import:R0603")
      (libsource (lib "eagle-import") (part "R-EU_R0603"))
    )
    (comp (ref "R78")
      (value "10K")
      (footprint "eagle-import:R1206")
      (libsource (lib "eagle-import") (part "R-EU_R1206"))
    )
    (comp (ref "R79")
      (value "10K")
      (footprint "eagle-import:R1206")
      (libsource (lib "eagle-import") (part "R-EU_R1206"))
    )
    (comp (ref "R80")
      (value "10K")
      (footprint "eagle-import:R0603")
      (libsource (lib "eagle-import") (part "R-EU_R0603"))
    )
    (comp (ref "R81")
      (value "2K")
      (footprint "eagle-import:R0603")
      (libsource (lib "eagle-import") (part "R-EU_R0603"))
    )
    (comp (ref "SOLENOID")
      (value "JP1E")
      (footprint "eagle-import:JP1")
      (libsource (lib "eagle-import") (part "JP1E"))
    )
    (comp (ref "SV1")
      (value "MLW40")
      (footprint "eagle-import:ML40")
      (libsource (lib "eagle-import") (part "MLW40"))
    )
    (comp (ref "TCRT_1")
      (value "TCRT5000")
      (footprint "eagle-import:TCRT5000")
      (libsource (lib "eagle-import") (part "TCRT5000"))
    )
    (comp (ref "TCRT_2")
      (value "TCRT5000")
      (footprint "eagle-import:TCRT5000")
      (libsource (lib "eagle-import") (part "TCRT5000"))
    )
    (comp (ref "TCRT_3")
      (value "TCRT5000")
      (footprint "eagle-import:TCRT5000")
      (libsource (lib "eagle-import") (part "TCRT5000"))
    )
    (comp (ref "TCRT_4")
      (value "TCRT5000")
      (footprint "eagle-import:TCRT5000")
      (libsource (lib "eagle-import") (part "TCRT5000"))
    )
    (comp (ref "TCRT_5")
      (value "TCRT5000")
      (footprint "eagle-import:TCRT5000")
      (libsource (lib "eagle-import") (part "TCRT5000"))
    )
    (comp (ref "TCRT_6")
      (value "TCRT5000")
      (footprint "eagle-import:TCRT5000")
      (libsource (lib "eagle-import") (part "TCRT5000"))
    )
    (comp (ref "TCRT_7")
      (value "TCRT5000")
      (footprint "eagle-import:TCRT5000")
      (libsource (lib "eagle-import") (part "TCRT5000"))
    )
    (comp (ref "TCRT_8")
      (value "TCRT5000")
      (footprint "eagle-import:TCRT5000")
      (libsource (lib "eagle-import") (part "TCRT5000"))
    )
    (comp (ref "TCRT_9")
      (value "TCRT5000")
      (footprint "eagle-import:TCRT5000")
      (libsource (lib "eagle-import") (part "TCRT5000"))
    )
    (comp (ref "TCRT_10")
      (value "TCRT5000")
      (footprint "eagle-import:TCRT5000")
      (libsource (lib "eagle-import") (part "TCRT5000"))
    )
    (comp (ref "TCRT_11")
      (value "TCRT5000")
      (footprint "eagle-import:TCRT5000")
      (libsource (lib "eagle-import") (part "TCRT5000"))
    )
    (comp (ref "TCRT_12")
      (value "TCRT5000")
      (footprint "eagle-import:TCRT5000")
      (libsource (lib "eagle-import") (part "TCRT5000"))
    )
    (comp (ref "TCRT_13")
      (value "TCRT5000")
      (footprint "eagle-import:TCRT5000")
      (libsource (lib "eagle-import") (part "TCRT5000"))
    )
    (comp (ref "TCRT_14")
      (value "TCRT5000")
      (footprint "eagle-import:TCRT5000")
      (libsource (lib "eagle-import") (part "TCRT5000"))
    )
    (comp (ref "TCRT_15")
      (value "TCRT5000")
      (footprint "eagle-import:TCRT5000")
      (libsource (lib "eagle-import") (part "TCRT5000"))
    )
    (comp (ref "TCRT_16")
      (value "TCRT5000")
      (footprint "eagle-import:TCRT5000")
      (libsource (lib "eagle-import") (part "TCRT5000"))
    )
    (comp (ref "TCRT_17")
      (value "TCRT5000")
      (footprint "eagle-import:TCRT5000")
      (libsource (lib "eagle-import") (part "TCRT5000"))
    )
    (comp (ref "TCRT_18")
      (value "TCRT5000")
      (footprint "eagle-import:TCRT5000")
      (libsource (lib "eagle-import") (part "TCRT5000"))
    )
    (comp (ref "TCRT_19")
      (value "TCRT5000")
      (footprint "eagle-import:TCRT5000")
      (libsource (lib "eagle-import") (part "TCRT5000"))
    )
    (comp (ref "TCRT_20")
      (value "TCRT5000")
      (footprint "eagle-import:TCRT5000")
      (libsource (lib "eagle-import") (part "TCRT5000"))
    )
    (comp (ref "TCRT_21")
      (value "TCRT5000")
      (footprint "eagle-import:TCRT5000")
      (libsource (lib "eagle-import") (part "TCRT5000"))
    )
    (comp (ref "TCRT_22")
      (value "TCRT5000")
      (footprint "eagle-import:TCRT5000")
      (libsource (lib "eagle-import") (part "TCRT5000"))
    )
    (comp (ref "TCRT_23")
      (value "TCRT5000")
      (footprint "eagle-import:TCRT5000")
      (libsource (lib "eagle-import") (part "TCRT5000"))
    )
    (comp (ref "TCRT_24")
      (value "TCRT5000")
      (footprint "eagle-import:TCRT5000")
      (libsource (lib "eagle-import") (part "TCRT5000"))
    )
    (comp (ref "TCRT_25")
      (value "TCRT5000")
      (footprint "eagle-import:TCRT5000")
      (libsource (lib "eagle-import") (part "TCRT5000"))
    )
    (comp (ref "TCRT_26")
      (value "TCRT5000")
      (footprint "eagle-import:TCRT5000")
      (libsource (lib "eagle-import") (part "TCRT5000"))
    )
    (comp (ref "TCRT_27")
      (value "TCRT5000")
      (footprint "eagle-import:TCRT5000")
      (libsource (lib "eagle-import") (part "TCRT5000"))
    )
    (comp (ref "TCRT_28")
      (value "TCRT5000")
      (footprint "eagle-import:TCRT5000")
      (libsource (lib "eagle-import") (part "TCRT5000"))
    )
    (comp (ref "TCRT_29")
      (value "TCRT5000")
      (footprint "eagle-import:TCRT5000")
      (libsource (lib "eagle-import") (part "TCRT5000"))
    )
    (comp (ref "TCRT_30")
      (value "TCRT5000")
      (footprint "eagle-import:TCRT5000")
      (libsource (lib "eagle-import") (part "TCRT5000"))
    )
    (comp (ref "TRIM")
      (value "3362W-1-103LF")
      (footprint "eagle-import:POT_3362W")
      (libsource (lib "eagle-import") (part "3362W-1-103LF"))
    )
    (comp (ref "U$4")
      (value "TERMINAL")
      (footprint "eagle-import:TERMINAL")
      (libsource (lib "eagle-import") (part "TERMINAL"))
    )
    (comp (ref "U$5")
      (value "TERMINAL")
      (footprint "eagle-import:TERMINAL")
      (libsource (lib "eagle-import") (part "TERMINAL"))
    )
    (comp (ref "Z1")
      (value "1n5824")
      (footprint "eagle-import:SUPRESSOR_SMAJ")
      (libsource (lib "eagle-import") (part "SUPRESSOR_TVS-UD-SMAJ"))
    )
    (comp (ref "Z2")
      (value "1n5824")
      (footprint "eagle-import:SUPRESSOR_SMAJ")
      (libsource (lib "eagle-import") (part "SUPRESSOR_TVS-UD-SMAJ"))
    )
  )
  (nets
    (net (code "1") (name "/~{CE}") (class "Default")
      (node (ref "!CE") (pin "2") (pinfunction "A2_2") (pintype "bidirectional"))
      (node (ref "AT28BV25628T") (pin "27") (pinfunction "~{CE}_27") (pintype "passive"))
    )
    (net (code "2") (name "/~{OE}") (class "Default")
      (node (ref "!OE") (pin "2") (pinfunction "A2_2") (pintype "bidirectional"))
      (node (ref "AT28BV25628T") (pin "1") (pinfunction "~{OE}_1") (pintype "output"))
    )
    (net (code "3") (name "/~{WE}") (class "Default")
      (node (ref "!WE") (pin "2") (pinfunction "A2_2") (pintype "bidirectional"))
      (node (ref "AT28BV25628T") (pin "6") (pinfunction "~{WE}_6") (pintype "passive"))
    )
    (net (code "4") (name "3.3V") (class "Default")
      (node (ref "C43") (pin "1") (pinfunction "1_1") (pintype "passive"))
      (node (ref "C44") (pin "1") (pinfunction "1_1") (pintype "passive"))
      (node (ref "C48") (pin "1") (pinfunction "1_1") (pintype "passive"))
      (node (ref "IC1") (pin "10") (pinfunction "OE_10") (pintype "bidirectional"))
      (node (ref "IC1") (pin "2") (pinfunction "VCCA_2") (pintype "bidirectional"))
      (node (ref "IC2") (pin "2") (pinfunction "VOUT_2") (pintype "output"))
      (node (ref "Q1") (pin "1") (pinfunction "G_1") (pintype "passive"))
      (node (ref "R73") (pin "1") (pinfunction "1_1") (pintype "passive"))
      (node (ref "SV1") (pin "28") (pinfunction "28_28") (pintype "passive"))
    )
    (net (code "5") (name "5V") (class "Default")
      (node (ref "!CE") (pin "3") (pinfunction "A3_3") (pintype "bidirectional"))
      (node (ref "!OE") (pin "3") (pinfunction "A3_3") (pintype "bidirectional"))
      (node (ref "!WE") (pin "3") (pinfunction "A3_3") (pintype "bidirectional"))
      (node (ref "AT28BV25628T") (pin "7") (pinfunction "VCC_7") (pintype "power_in"))
      (node (ref "C10") (pin "1") (pinfunction "1_1") (pintype "passive"))
      (node (ref "C11") (pin "1") (pinfunction "1_1") (pintype "passive"))
      (node (ref "C12") (pin "1") (pinfunction "1_1") (pintype "passive"))
      (node (ref "C13") (pin "1") (pinfunction "1_1") (pintype "passive"))
      (node (ref "C14") (pin "1") (pinfunction "1_1") (pintype "passive"))
      (node (ref "C15") (pin "1") (pinfunction "1_1") (pintype "passive"))
      (node (ref "C16") (pin "1") (pinfunction "1_1") (pintype "passive"))
      (node (ref "C17") (pin "1") (pinfunction "1_1") (pintype "passive"))
      (node (ref "C18") (pin "1") (pinfunction "1_1") (pintype "passive"))
      (node (ref "C19") (pin "1") (pinfunction "1_1") (pintype "passive"))
      (node (ref "C2") (pin "1") (pinfunction "1_1") (pintype "passive"))
      (node (ref "C20") (pin "1") (pinfunction "1_1") (pintype "passive"))
      (node (ref "C21") (pin "1") (pinfunction "1_1") (pintype "passive"))
      (node (ref "C22") (pin "1") (pinfunction "1_1") (pintype "passive"))
      (node (ref "C23") (pin "1") (pinfunction "1_1") (pintype "passive"))
      (node (ref "C24") (pin "1") (pinfunction "1_1") (pintype "passive"))
      (node (ref "C25") (pin "1") (pinfunction "1_1") (pintype "passive"))
      (node (ref "C26") (pin "1") (pinfunction "1_1") (pintype "passive"))
      (node (ref "C27") (pin "1") (pinfunction "1_1") (pintype "passive"))
      (node (ref "C28") (pin "1") (pinfunction "1_1") (pintype "passive"))
      (node (ref "C29") (pin "1") (pinfunction "1_1") (pintype "passive"))
      (node (ref "C3") (pin "1") (pinfunction "1_1") (pintype "passive"))
      (node (ref "C30") (pin "1") (pinfunction "1_1") (pintype "passive"))
      (node (ref "C31") (pin "1") (pinfunction "1_1") (pintype "passive"))
      (node (ref "C32") (pin "1") (pinfunction "1_1") (pintype "passive"))
      (node (ref "C33") (pin "1") (pinfunction "1_1") (pintype "passive"))
      (node (ref "C34") (pin "1") (pinfunction "1_1") (pintype "passive"))
      (node (ref "C35") (pin "1") (pinfunction "1_1") (pintype "passive"))
      (node (ref "C36") (pin "1") (pinfunction "1_1") (pintype "passive"))
      (node (ref "C37") (pin "1") (pinfunction "1_1") (pintype "passive"))
      (node (ref "C38") (pin "1") (pinfunction "1_1") (pintype "passive"))
      (node (ref "C39") (pin "1") (pinfunction "1_1") (pintype "passive"))
      (node (ref "C40") (pin "1") (pinfunction "1_1") (pintype "passive"))
      (node (ref "C41") (pin "1") (pinfunction "1_1") (pintype "passive"))
      (node (ref "C42") (pin "1") (pinfunction "1_1") (pintype "passive"))
      (node (ref "C47") (pin "1") (pinfunction "1_1") (pintype "passive"))
      (node (ref "C51") (pin "1") (pinfunction "1_1") (pintype "passive"))
      (node (ref "C7") (pin "1") (pinfunction "1_1") (pintype "passive"))
      (node (ref "C8") (pin "1") (pinfunction "1_1") (pintype "passive"))
      (node (ref "C9") (pin "1") (pinfunction "1_1") (pintype "passive"))
      (node (ref "COMP_1") (pin "5") (pinfunction "5_5") (pintype "passive"))
      (node (ref "COMP_10") (pin "5") (pinfunction "5_5") (pintype "passive"))
      (node (ref "COMP_11") (pin "5") (pinfunction "5_5") (pintype "passive"))
      (node (ref "COMP_12") (pin "5") (pinfunction "5_5") (pintype "passive"))
      (node (ref "COMP_13") (pin "5") (pinfunction "5_5") (pintype "passive"))
      (node (ref "COMP_14") (pin "5") (pinfunction "5_5") (pintype "passive"))
      (node (ref "COMP_15") (pin "5") (pinfunction "5_5") (pintype "passive"))
      (node (ref "COMP_16") (pin "5") (pinfunction "5_5") (pintype "passive"))
      (node (ref "COMP_17") (pin "5") (pinfunction "5_5") (pintype "passive"))
      (node (ref "COMP_18") (pin "5") (pinfunction "5_5") (pintype "passive"))
      (node (ref "COMP_19") (pin "5") (pinfunction "5_5") (pintype "passive"))
      (node (ref "COMP_2") (pin "5") (pinfunction "5_5") (pintype "passive"))
      (node (ref "COMP_20") (pin "5") (pinfunction "5_5") (pintype "passive"))
      (node (ref "COMP_21") (pin "5") (pinfunction "5_5") (pintype "passive"))
      (node (ref "COMP_22") (pin "5") (pinfunction "5_5") (pintype "passive"))
      (node (ref "COMP_23") (pin "5") (pinfunction "5_5") (pintype "passive"))
      (node (ref "COMP_24") (pin "5") (pinfunction "5_5") (pintype "passive"))
      (node (ref "COMP_25") (pin "5") (pinfunction "5_5") (pintype "passive"))
      (node (ref "COMP_26") (pin "5") (pinfunction "5_5") (pintype "passive"))
      (node (ref "COMP_27") (pin "5") (pinfunction "5_5") (pintype "passive"))
      (node (ref "COMP_28") (pin "5") (pinfunction "5_5") (pintype "passive"))
      (node (ref "COMP_29") (pin "5") (pinfunction "5_5") (pintype "passive"))
      (node (ref "COMP_3") (pin "5") (pinfunction "5_5") (pintype "passive"))
      (node (ref "COMP_30") (pin "5") (pinfunction "5_5") (pintype "passive"))
      (node (ref "COMP_4") (pin "5") (pinfunction "5_5") (pintype "passive"))
      (node (ref "COMP_5") (pin "5") (pinfunction "5_5") (pintype "passive"))
      (node (ref "COMP_6") (pin "5") (pinfunction "5_5") (pintype "passive"))
      (node (ref "COMP_7") (pin "5") (pinfunction "5_5") (pintype "passive"))
      (node (ref "COMP_8") (pin "5") (pinfunction "5_5") (pintype "passive"))
      (node (ref "COMP_9") (pin "5") (pinfunction "5_5") (pintype "passive"))
      (node (ref "IC1") (pin "19") (pinfunction "VCCB_19") (pintype "bidirectional"))
      (node (ref "IO2") (pin "4") (pinfunction "FB_4") (pintype "input"))
      (node (ref "L2") (pin "2") (pinfunction "2_2") (pintype "passive"))
      (node (ref "OR_1") (pin "14") (pinfunction "VCC_14") (pintype "power_in"))
      (node (ref "OR_2") (pin "14") (pinfunction "VCC_14") (pintype "power_in"))
      (node (ref "OR_3") (pin "14") (pinfunction "VCC_14") (pintype "power_in"))
      (node (ref "OR_4") (pin "14") (pinfunction "VCC_14") (pintype "power_in"))
      (node (ref "OR_5") (pin "14") (pinfunction "VCC_14") (pintype "power_in"))
      (node (ref "OR_6") (pin "14") (pinfunction "VCC_14") (pintype "power_in"))
      (node (ref "R77") (pin "1") (pinfunction "1_1") (pintype "passive"))
      (node (ref "TCRT_1") (pin "A") (pinfunction "ANODE_A") (pintype "passive"))
      (node (ref "TCRT_1") (pin "C") (pinfunction "COLLECTOR_C") (pintype "passive"))
      (node (ref "TCRT_10") (pin "A") (pinfunction "ANODE_A") (pintype "passive"))
      (node (ref "TCRT_10") (pin "C") (pinfunction "COLLECTOR_C") (pintype "passive"))
      (node (ref "TCRT_11") (pin "A") (pinfunction "ANODE_A") (pintype "passive"))
      (node (ref "TCRT_11") (pin "C") (pinfunction "COLLECTOR_C") (pintype "passive"))
      (node (ref "TCRT_12") (pin "A") (pinfunction "ANODE_A") (pintype "passive"))
      (node (ref "TCRT_12") (pin "C") (pinfunction "COLLECTOR_C") (pintype "passive"))
      (node (ref "TCRT_13") (pin "A") (pinfunction "ANODE_A") (pintype "passive"))
      (node (ref "TCRT_13") (pin "C") (pinfunction "COLLECTOR_C") (pintype "passive"))
      (node (ref "TCRT_14") (pin "A") (pinfunction "ANODE_A") (pintype "passive"))
      (node (ref "TCRT_14") (pin "C") (pinfunction "COLLECTOR_C") (pintype "passive"))
      (node (ref "TCRT_15") (pin "A") (pinfunction "ANODE_A") (pintype "passive"))
      (node (ref "TCRT_15") (pin "C") (pinfunction "COLLECTOR_C") (pintype "passive"))
      (node (ref "TCRT_16") (pin "A") (pinfunction "ANODE_A") (pintype "passive"))
      (node (ref "TCRT_16") (pin "C") (pinfunction "COLLECTOR_C") (pintype "passive"))
      (node (ref "TCRT_17") (pin "A") (pinfunction "ANODE_A") (pintype "passive"))
      (node (ref "TCRT_17") (pin "C") (pinfunction "COLLECTOR_C") (pintype "passive"))
      (node (ref "TCRT_18") (pin "A") (pinfunction "ANODE_A") (pintype "passive"))
      (node (ref "TCRT_18") (pin "C") (pinfunction "COLLECTOR_C") (pintype "passive"))
      (node (ref "TCRT_19") (pin "A") (pinfunction "ANODE_A") (pintype "passive"))
      (node (ref "TCRT_19") (pin "C") (pinfunction "COLLECTOR_C") (pintype "passive"))
      (node (ref "TCRT_2") (pin "A") (pinfunction "ANODE_A") (pintype "passive"))
      (node (ref "TCRT_2") (pin "C") (pinfunction "COLLECTOR_C") (pintype "passive"))
      (node (ref "TCRT_20") (pin "A") (pinfunction "ANODE_A") (pintype "passive"))
      (node (ref "TCRT_20") (pin "C") (pinfunction "COLLECTOR_C") (pintype "passive"))
      (node (ref "TCRT_21") (pin "A") (pinfunction "ANODE_A") (pintype "passive"))
      (node (ref "TCRT_21") (pin "C") (pinfunction "COLLECTOR_C") (pintype "passive"))
      (node (ref "TCRT_22") (pin "A") (pinfunction "ANODE_A") (pintype "passive"))
      (node (ref "TCRT_22") (pin "C") (pinfunction "COLLECTOR_C") (pintype "passive"))
      (node (ref "TCRT_23") (pin "A") (pinfunction "ANODE_A") (pintype "passive"))
      (node (ref "TCRT_23") (pin "C") (pinfunction "COLLECTOR_C") (pintype "passive"))
      (node (ref "TCRT_24") (pin "A") (pinfunction "ANODE_A") (pintype "passive"))
      (node (ref "TCRT_24") (pin "C") (pinfunction "COLLECTOR_C") (pintype "passive"))
      (node (ref "TCRT_25") (pin "A") (pinfunction "ANODE_A") (pintype "passive"))
      (node (ref "TCRT_25") (pin "C") (pinfunction "COLLECTOR_C") (pintype "passive"))
      (node (ref "TCRT_26") (pin "A") (pinfunction "ANODE_A") (pintype "passive"))
      (node (ref "TCRT_26") (pin "C") (pinfunction "COLLECTOR_C") (pintype "passive"))
      (node (ref "TCRT_27") (pin "A") (pinfunction "ANODE_A") (pintype "passive"))
      (node (ref "TCRT_27") (pin "C") (pinfunction "COLLECTOR_C") (pintype "passive"))
      (node (ref "TCRT_28") (pin "A") (pinfunction "ANODE_A") (pintype "passive"))
      (node (ref "TCRT_28") (pin "C") (pinfunction "COLLECTOR_C") (pintype "passive"))
      (node (ref "TCRT_29") (pin "A") (pinfunction "ANODE_A") (pintype "passive"))
      (node (ref "TCRT_29") (pin "C") (pinfunction "COLLECTOR_C") (pintype "passive"))
      (node (ref "TCRT_3") (pin "A") (pinfunction "ANODE_A") (pintype "passive"))
      (node (ref "TCRT_3") (pin "C") (pinfunction "COLLECTOR_C") (pintype "passive"))
      (node (ref "TCRT_30") (pin "A") (pinfunction "ANODE_A") (pintype "passive"))
      (node (ref "TCRT_30") (pin "C") (pinfunction "COLLECTOR_C") (pintype "passive"))
      (node (ref "TCRT_4") (pin "A") (pinfunction "ANODE_A") (pintype "passive"))
      (node (ref "TCRT_4") (pin "C") (pinfunction "COLLECTOR_C") (pintype "passive"))
      (node (ref "TCRT_5") (pin "A") (pinfunction "ANODE_A") (pintype "passive"))
      (node (ref "TCRT_5") (pin "C") (pinfunction "COLLECTOR_C") (pintype "passive"))
      (node (ref "TCRT_6") (pin "A") (pinfunction "ANODE_A") (pintype "passive"))
      (node (ref "TCRT_6") (pin "C") (pinfunction "COLLECTOR_C") (pintype "passive"))
      (node (ref "TCRT_7") (pin "A") (pinfunction "ANODE_A") (pintype "passive"))
      (node (ref "TCRT_7") (pin "C") (pinfunction "COLLECTOR_C") (pintype "passive"))
      (node (ref "TCRT_8") (pin "A") (pinfunction "ANODE_A") (pintype "passive"))
      (node (ref "TCRT_8") (pin "C") (pinfunction "COLLECTOR_C") (pintype "passive"))
      (node (ref "TCRT_9") (pin "A") (pinfunction "ANODE_A") (pintype "passive"))
      (node (ref "TCRT_9") (pin "C") (pinfunction "COLLECTOR_C") (pintype "passive"))
      (node (ref "TRIM") (pin "3") (pinfunction "3_3") (pintype "passive"))
    )
    (net (code "6") (name "5V_JATSON") (class "Default")
      (node (ref "C4") (pin "1") (pinfunction "1_1") (pintype "passive"))
      (node (ref "C6") (pin "1") (pinfunction "1_1") (pintype "passive"))
      (node (ref "IO1") (pin "4") (pinfunction "FB_4") (pintype "input"))
      (node (ref "L1") (pin "2") (pinfunction "2_2") (pintype "passive"))
      (node (ref "SV1") (pin "22") (pinfunction "22_22") (pintype "passive"))
      (node (ref "SV1") (pin "24") (pinfunction "24_24") (pintype "passive"))
      (node (ref "SV1") (pin "26") (pinfunction "26_26") (pintype "passive"))
    )
    (net (code "7") (name "A0") (class "Default")
      (node (ref "A0") (pin "TP") (pinfunction "TP_TP") (pintype "input"))
      (node (ref "AT28BV25628T") (pin "17") (pinfunction "A0_17") (pintype "passive"))
      (node (ref "R63") (pin "1") (pinfunction "1_1") (pintype "passive"))
    )
    (net (code "8") (name "A1") (class "Default")
      (node (ref "A1") (pin "TP") (pinfunction "TP_TP") (pintype "input"))
      (node (ref "AT28BV25628T") (pin "16") (pinfunction "A1_16") (pintype "passive"))
      (node (ref "R64") (pin "1") (pinfunction "1_1") (pintype "passive"))
    )
    (net (code "9") (name "A2") (class "Default")
      (node (ref "A2") (pin "TP") (pinfunction "TP_TP") (pintype "input"))
      (node (ref "AT28BV25628T") (pin "15") (pinfunction "A2_15") (pintype "passive"))
      (node (ref "R62") (pin "1") (pinfunction "1_1") (pintype "passive"))
    )
    (net (code "10") (name "A3") (class "Default")
      (node (ref "A3") (pin "TP") (pinfunction "TP_TP") (pintype "input"))
      (node (ref "AT28BV25628T") (pin "14") (pinfunction "A3_14") (pintype "passive"))
      (node (ref "R61") (pin "1") (pinfunction "1_1") (pintype "passive"))
    )
    (net (code "11") (name "A4") (class "Default")
      (node (ref "A4") (pin "TP") (pinfunction "TP_TP") (pintype "input"))
      (node (ref "AT28BV25628T") (pin "13") (pinfunction "A4_13") (pintype "passive"))
      (node (ref "R68") (pin "1") (pinfunction "1_1") (pintype "passive"))
    )
    (net (code "12") (name "A5") (class "Default")
      (node (ref "A5") (pin "TP") (pinfunction "TP_TP") (pintype "input"))
      (node (ref "AT28BV25628T") (pin "12") (pinfunction "A5_12") (pintype "passive"))
      (node (ref "R67") (pin "1") (pinfunction "1_1") (pintype "passive"))
    )
    (net (code "13") (name "A6") (class "Default")
      (node (ref "A6") (pin "TP") (pinfunction "TP_TP") (pintype "input"))
      (node (ref "AT28BV25628T") (pin "11") (pinfunction "A6_11") (pintype "passive"))
      (node (ref "R66") (pin "1") (pinfunction "1_1") (pintype "passive"))
    )
    (net (code "14") (name "A7") (class "Default")
      (node (ref "A7") (pin "TP") (pinfunction "TP_TP") (pintype "input"))
      (node (ref "AT28BV25628T") (pin "10") (pinfunction "A7_10") (pintype "passive"))
      (node (ref "R65") (pin "1") (pinfunction "1_1") (pintype "passive"))
    )
    (net (code "15") (name "A8") (class "Default")
      (node (ref "A8") (pin "TP") (pinfunction "TP_TP") (pintype "input"))
      (node (ref "AT28BV25628T") (pin "4") (pinfunction "A8_4") (pintype "passive"))
      (node (ref "R72") (pin "1") (pinfunction "1_1") (pintype "passive"))
    )
    (net (code "16") (name "A9") (class "Default")
      (node (ref "A9") (pin "TP") (pinfunction "TP_TP") (pintype "input"))
      (node (ref "AT28BV25628T") (pin "3") (pinfunction "A9_3") (pintype "passive"))
      (node (ref "R71") (pin "1") (pinfunction "1_1") (pintype "passive"))
    )
    (net (code "17") (name "A10") (class "Default")
      (node (ref "A10") (pin "TP") (pinfunction "TP_TP") (pintype "input"))
      (node (ref "AT28BV25628T") (pin "28") (pinfunction "A10_28") (pintype "passive"))
      (node (ref "R70") (pin "1") (pinfunction "1_1") (pintype "passive"))
    )
    (net (code "18") (name "A11") (class "Default")
      (node (ref "A11") (pin "TP") (pinfunction "TP_TP") (pintype "input"))
      (node (ref "AT28BV25628T") (pin "2") (pinfunction "A11_2") (pintype "passive"))
      (node (ref "R69") (pin "1") (pinfunction "1_1") (pintype "passive"))
    )
    (net (code "19") (name "A12") (class "Default")
      (node (ref "A12") (pin "TP") (pinfunction "TP_TP") (pintype "input"))
      (node (ref "AT28BV25628T") (pin "9") (pinfunction "A12_9") (pintype "passive"))
      (node (ref "R76") (pin "1") (pinfunction "1_1") (pintype "passive"))
    )
    (net (code "20") (name "A13") (class "Default")
      (node (ref "A13") (pin "TP") (pinfunction "TP_TP") (pintype "input"))
      (node (ref "AT28BV25628T") (pin "5") (pinfunction "A13_5") (pintype "passive"))
      (node (ref "R75") (pin "1") (pinfunction "1_1") (pintype "passive"))
    )
    (net (code "21") (name "A14") (class "Default")
      (node (ref "A14") (pin "TP") (pinfunction "TP_TP") (pintype "input"))
      (node (ref "AT28BV25628T") (pin "8") (pinfunction "A14_8") (pintype "passive"))
      (node (ref "R74") (pin "1") (pinfunction "1_1") (pintype "passive"))
    )
    (net (code "22") (name "BAT") (class "Default")
      (node (ref "C1") (pin "1") (pinfunction "1_1") (pintype "passive"))
      (node (ref "C45") (pin "1") (pinfunction "1_1") (pintype "passive"))
      (node (ref "C46") (pin "1") (pinfunction "1_1") (pintype "passive"))
      (node (ref "C5") (pin "1") (pinfunction "1_1") (pintype "passive"))
      (node (ref "IC2") (pin "3") (pinfunction "VIN_3") (pintype "input"))
      (node (ref "IO1") (pin "1") (pinfunction "IN_1") (pintype "input"))
      (node (ref "IO2") (pin "1") (pinfunction "IN_1") (pintype "input"))
      (node (ref "MAIN_POWER") (pin "3") (pinfunction "3-ON_3") (pintype "passive"))
    )
    (net (code "23") (name "BAT_UP") (class "Default")
      (node (ref "FUSE1") (pin "1") (pinfunction "1_1") (pintype "passive"))
      (node (ref "SV1") (pin "11") (pinfunction "11_11") (pintype "passive"))
      (node (ref "SV1") (pin "13") (pinfunction "13_13") (pintype "passive"))
      (node (ref "SV1") (pin "15") (pinfunction "15_15") (pintype "passive"))
      (node (ref "SV1") (pin "17") (pinfunction "17_17") (pintype "passive"))
      (node (ref "SV1") (pin "19") (pinfunction "19_19") (pintype "passive"))
      (node (ref "SV1") (pin "21") (pinfunction "21_21") (pintype "passive"))
      (node (ref "SV1") (pin "23") (pinfunction "23_23") (pintype "passive"))
      (node (ref "SV1") (pin "25") (pinfunction "25_25") (pintype "passive"))
      (node (ref "SV1") (pin "27") (pinfunction "27_27") (pintype "passive"))
      (node (ref "SV1") (pin "9") (pinfunction "9_9") (pintype "passive"))
    )
    (net (code "24") (name "CAPACITOR") (class "Default")
      (node (ref "Q3") (pin "G") (pinfunction "G_G") (pintype "passive"))
      (node (ref "R79") (pin "2") (pinfunction "2_2") (pintype "passive"))
      (node (ref "SV1") (pin "30") (pinfunction "30_30") (pintype "passive"))
    )
    (net (code "25") (name "GND") (class "Default")
      (node (ref "!CE") (pin "1") (pinfunction "A1_1") (pintype "bidirectional"))
      (node (ref "!OE") (pin "1") (pinfunction "A1_1") (pintype "bidirectional"))
      (node (ref "!WE") (pin "1") (pinfunction "A1_1") (pintype "bidirectional"))
      (node (ref "AT28BV25628T") (pin "21") (pinfunction "GND_21") (pintype "power_in"))
      (node (ref "C1") (pin "2") (pinfunction "2_2") (pintype "passive"))
      (node (ref "C10") (pin "2") (pinfunction "2_2") (pintype "passive"))
      (node (ref "C11") (pin "2") (pinfunction "2_2") (pintype "passive"))
      (node (ref "C12") (pin "2") (pinfunction "2_2") (pintype "passive"))
      (node (ref "C13") (pin "2") (pinfunction "2_2") (pintype "passive"))
      (node (ref "C14") (pin "2") (pinfunction "2_2") (pintype "passive"))
      (node (ref "C15") (pin "2") (pinfunction "2_2") (pintype "passive"))
      (node (ref "C16") (pin "2") (pinfunction "2_2") (pintype "passive"))
      (node (ref "C17") (pin "2") (pinfunction "2_2") (pintype "passive"))
      (node (ref "C18") (pin "2") (pinfunction "2_2") (pintype "passive"))
      (node (ref "C19") (pin "2") (pinfunction "2_2") (pintype "passive"))
      (node (ref "C2") (pin "2") (pinfunction "2_2") (pintype "passive"))
      (node (ref "C20") (pin "2") (pinfunction "2_2") (pintype "passive"))
      (node (ref "C21") (pin "2") (pinfunction "2_2") (pintype "passive"))
      (node (ref "C22") (pin "2") (pinfunction "2_2") (pintype "passive"))
      (node (ref "C23") (pin "2") (pinfunction "2_2") (pintype "passive"))
      (node (ref "C24") (pin "2") (pinfunction "2_2") (pintype "passive"))
      (node (ref "C25") (pin "2") (pinfunction "2_2") (pintype "passive"))
      (node (ref "C26") (pin "2") (pinfunction "2_2") (pintype "passive"))
      (node (ref "C27") (pin "2") (pinfunction "2_2") (pintype "passive"))
      (node (ref "C28") (pin "2") (pinfunction "2_2") (pintype "passive"))
      (node (ref "C29") (pin "2") (pinfunction "2_2") (pintype "passive"))
      (node (ref "C3") (pin "2") (pinfunction "2_2") (pintype "passive"))
      (node (ref "C30") (pin "2") (pinfunction "2_2") (pintype "passive"))
      (node (ref "C31") (pin "2") (pinfunction "2_2") (pintype "passive"))
      (node (ref "C32") (pin "2") (pinfunction "2_2") (pintype "passive"))
      (node (ref "C33") (pin "2") (pinfunction "2_2") (pintype "passive"))
      (node (ref "C34") (pin "2") (pinfunction "2_2") (pintype "passive"))
      (node (ref "C35") (pin "2") (pinfunction "2_2") (pintype "passive"))
      (node (ref "C36") (pin "2") (pinfunction "2_2") (pintype "passive"))
      (node (ref "C37") (pin "2") (pinfunction "2_2") (pintype "passive"))
      (node (ref "C38") (pin "2") (pinfunction "2_2") (pintype "passive"))
      (node (ref "C39") (pin "2") (pinfunction "2_2") (pintype "passive"))
      (node (ref "C4") (pin "2") (pinfunction "2_2") (pintype "passive"))
      (node (ref "C40") (pin "2") (pinfunction "2_2") (pintype "passive"))
      (node (ref "C41") (pin "2") (pinfunction "2_2") (pintype "passive"))
      (node (ref "C42") (pin "2") (pinfunction "2_2") (pintype "passive"))
      (node (ref "C43") (pin "2") (pinfunction "2_2") (pintype "passive"))
      (node (ref "C44") (pin "2") (pinfunction "2_2") (pintype "passive"))
      (node (ref "C45") (pin "2") (pinfunction "2_2") (pintype "passive"))
      (node (ref "C46") (pin "2") (pinfunction "2_2") (pintype "passive"))
      (node (ref "C47") (pin "2") (pinfunction "2_2") (pintype "passive"))
      (node (ref "C48") (pin "2") (pinfunction "2_2") (pintype "passive"))
      (node (ref "C49") (pin "-") (pinfunction "-_-") (pintype "passive"))
      (node (ref "C5") (pin "2") (pinfunction "2_2") (pintype "passive"))
      (node (ref "C50") (pin "-") (pinfunction "-_-") (pintype "passive"))
      (node (ref "C51") (pin "2") (pinfunction "2_2") (pintype "passive"))
      (node (ref "C52") (pin "1") (pinfunction "1_1") (pintype "passive"))
      (node (ref "C6") (pin "2") (pinfunction "2_2") (pintype "passive"))
      (node (ref "C7") (pin "2") (pinfunction "2_2") (pintype "passive"))
      (node (ref "C8") (pin "2") (pinfunction "2_2") (pintype "passive"))
      (node (ref "C9") (pin "2") (pinfunction "2_2") (pintype "passive"))
      (node (ref "COMP_1") (pin "2") (pinfunction "2_2") (pintype "passive"))
      (node (ref "COMP_10") (pin "2") (pinfunction "2_2") (pintype "passive"))
      (node (ref "COMP_11") (pin "2") (pinfunction "2_2") (pintype "passive"))
      (node (ref "COMP_12") (pin "2") (pinfunction "2_2") (pintype "passive"))
      (node (ref "COMP_13") (pin "2") (pinfunction "2_2") (pintype "passive"))
      (node (ref "COMP_14") (pin "2") (pinfunction "2_2") (pintype "passive"))
      (node (ref "COMP_15") (pin "2") (pinfunction "2_2") (pintype "passive"))
      (node (ref "COMP_16") (pin "2") (pinfunction "2_2") (pintype "passive"))
      (node (ref "COMP_17") (pin "2") (pinfunction "2_2") (pintype "passive"))
      (node (ref "COMP_18") (pin "2") (pinfunction "2_2") (pintype "passive"))
      (node (ref "COMP_19") (pin "2") (pinfunction "2_2") (pintype "passive"))
      (node (ref "COMP_2") (pin "2") (pinfunction "2_2") (pintype "passive"))
      (node (ref "COMP_20") (pin "2") (pinfunction "2_2") (pintype "passive"))
      (node (ref "COMP_21") (pin "2") (pinfunction "2_2") (pintype "passive"))
      (node (ref "COMP_22") (pin "2") (pinfunction "2_2") (pintype "passive"))
      (node (ref "COMP_23") (pin "2") (pinfunction "2_2") (pintype "passive"))
      (node (ref "COMP_24") (pin "2") (pinfunction "2_2") (pintype "passive"))
      (node (ref "COMP_25") (pin "2") (pinfunction "2_2") (pintype "passive"))
      (node (ref "COMP_26") (pin "2") (pinfunction "2_2") (pintype "passive"))
      (node (ref "COMP_27") (pin "2") (pinfunction "2_2") (pintype "passive"))
      (node (ref "COMP_28") (pin "2") (pinfunction "2_2") (pintype "passive"))
      (node (ref "COMP_29") (pin "2") (pinfunction "2_2") (pintype "passive"))
      (node (ref "COMP_3") (pin "2") (pinfunction "2_2") (pintype "passive"))
      (node (ref "COMP_30") (pin "2") (pinfunction "2_2") (pintype "passive"))
      (node (ref "COMP_4") (pin "2") (pinfunction "2_2") (pintype "passive"))
      (node (ref "COMP_5") (pin "2") (pinfunction "2_2") (pintype "passive"))
      (node (ref "COMP_6") (pin "2") (pinfunction "2_2") (pintype "passive"))
      (node (ref "COMP_7") (pin "2") (pinfunction "2_2") (pintype "passive"))
      (node (ref "COMP_8") (pin "2") (pinfunction "2_2") (pintype "passive"))
      (node (ref "COMP_9") (pin "2") (pinfunction "2_2") (pintype "passive"))
      (node (ref "IC1") (pin "11") (pinfunction "GND_11") (pintype "bidirectional"))
      (node (ref "IC2") (pin "1") (pinfunction "GND_1") (pintype "power_in"))
      (node (ref "IO1") (pin "3") (pinfunction "GND_3") (pintype "power_in"))
      (node (ref "IO1") (pin "5") (pinfunction "EN_5") (pintype "input"))
      (node (ref "IO1") (pin "6") (pinfunction "GND_6") (pintype "power_in"))
      (node (ref "IO2") (pin "3") (pinfunction "GND_3") (pintype "power_in"))
      (node (ref "IO2") (pin "5") (pinfunction "EN_5") (pintype "input"))
      (node (ref "IO2") (pin "6") (pinfunction "GND_6") (pintype "power_in"))
      (node (ref "OR_1") (pin "7") (pinfunction "GND_7") (pintype "power_in"))
      (node (ref "OR_2") (pin "7") (pinfunction "GND_7") (pintype "power_in"))
      (node (ref "OR_3") (pin "7") (pinfunction "GND_7") (pintype "power_in"))
      (node (ref "OR_4") (pin "7") (pinfunction "GND_7") (pintype "power_in"))
      (node (ref "OR_5") (pin "7") (pinfunction "GND_7") (pintype "power_in"))
      (node (ref "OR_6") (pin "7") (pinfunction "GND_7") (pintype "power_in"))
      (node (ref "R1") (pin "2") (pinfunction "2_2") (pintype "passive"))
      (node (ref "R10") (pin "2") (pinfunction "2_2") (pintype "passive"))
      (node (ref "R11") (pin "2") (pinfunction "2_2") (pintype "passive"))
      (node (ref "R12") (pin "2") (pinfunction "2_2") (pintype "passive"))
      (node (ref "R13") (pin "2") (pinfunction "2_2") (pintype "passive"))
      (node (ref "R14") (pin "2") (pinfunction "2_2") (pintype "passive"))
      (node (ref "R15") (pin "2") (pinfunction "2_2") (pintype "passive"))
      (node (ref "R16") (pin "2") (pinfunction "2_2") (pintype "passive"))
      (node (ref "R17") (pin "2") (pinfunction "2_2") (pintype "passive"))
      (node (ref "R18") (pin "2") (pinfunction "2_2") (pintype "passive"))
      (node (ref "R19") (pin "2") (pinfunction "2_2") (pintype "passive"))
      (node (ref "R2") (pin "2") (pinfunction "2_2") (pintype "passive"))
      (node (ref "R20") (pin "2") (pinfunction "2_2") (pintype "passive"))
      (node (ref "R21") (pin "2") (pinfunction "2_2") (pintype "passive"))
      (node (ref "R22") (pin "2") (pinfunction "2_2") (pintype "passive"))
      (node (ref "R23") (pin "2") (pinfunction "2_2") (pintype "passive"))
      (node (ref "R24") (pin "2") (pinfunction "2_2") (pintype "passive"))
      (node (ref "R25") (pin "2") (pinfunction "2_2") (pintype "passive"))
      (node (ref "R26") (pin "2") (pinfunction "2_2") (pintype "passive"))
      (node (ref "R27") (pin "2") (pinfunction "2_2") (pintype "passive"))
      (node (ref "R28") (pin "2") (pinfunction "2_2") (pintype "passive"))
      (node (ref "R29") (pin "2") (pinfunction "2_2") (pintype "passive"))
      (node (ref "R3") (pin "2") (pinfunction "2_2") (pintype "passive"))
      (node (ref "R30") (pin "2") (pinfunction "2_2") (pintype "passive"))
      (node (ref "R31") (pin "2") (pinfunction "2_2") (pintype "passive"))
      (node (ref "R32") (pin "2") (pinfunction "2_2") (pintype "passive"))
      (node (ref "R33") (pin "2") (pinfunction "2_2") (pintype "passive"))
      (node (ref "R34") (pin "2") (pinfunction "2_2") (pintype "passive"))
      (node (ref "R35") (pin "2") (pinfunction "2_2") (pintype "passive"))
      (node (ref "R36") (pin "2") (pinfunction "2_2") (pintype "passive"))
      (node (ref "R37") (pin "2") (pinfunction "2_2") (pintype "passive"))
      (node (ref "R38") (pin "2") (pinfunction "2_2") (pintype "passive"))
      (node (ref "R39") (pin "2") (pinfunction "2_2") (pintype "passive"))
      (node (ref "R4") (pin "2") (pinfunction "2_2") (pintype "passive"))
      (node (ref "R40") (pin "2") (pinfunction "2_2") (pintype "passive"))
      (node (ref "R41") (pin "2") (pinfunction "2_2") (pintype "passive"))
      (node (ref "R42") (pin "2") (pinfunction "2_2") (pintype "passive"))
      (node (ref "R43") (pin "2") (pinfunction "2_2") (pintype "passive"))
      (node (ref "R44") (pin "2") (pinfunction "2_2") (pintype "passive"))
      (node (ref "R45") (pin "2") (pinfunction "2_2") (pintype "passive"))
      (node (ref "R46") (pin "2") (pinfunction "2_2") (pintype "passive"))
      (node (ref "R47") (pin "2") (pinfunction "2_2") (pintype "passive"))
      (node (ref "R48") (pin "2") (pinfunction "2_2") (pintype "passive"))
      (node (ref "R49") (pin "2") (pinfunction "2_2") (pintype "passive"))
      (node (ref "R5") (pin "2") (pinfunction "2_2") (pintype "passive"))
      (node (ref "R50") (pin "2") (pinfunction "2_2") (pintype "passive"))
      (node (ref "R51") (pin "2") (pinfunction "2_2") (pintype "passive"))
      (node (ref "R52") (pin "2") (pinfunction "2_2") (pintype "passive"))
      (node (ref "R53") (pin "2") (pinfunction "2_2") (pintype "passive"))
      (node (ref "R54") (pin "2") (pinfunction "2_2") (pintype "passive"))
      (node (ref "R55") (pin "2") (pinfunction "2_2") (pintype "passive"))
      (node (ref "R56") (pin "2") (pinfunction "2_2") (pintype "passive"))
      (node (ref "R57") (pin "2") (pinfunction "2_2") (pintype "passive"))
      (node (ref "R58") (pin "2") (pinfunction "2_2") (pintype "passive"))
      (node (ref "R59") (pin "2") (pinfunction "2_2") (pintype "passive"))
      (node (ref "R6") (pin "2") (pinfunction "2_2") (pintype "passive"))
      (node (ref "R60") (pin "2") (pinfunction "2_2") (pintype "passive"))
      (node (ref "R7") (pin "2") (pinfunction "2_2") (pintype "passive"))
      (node (ref "R78") (pin "1") (pinfunction "1_1") (pintype "passive"))
      (node (ref "R79") (pin "1") (pinfunction "1_1") (pintype "passive"))
      (node (ref "R8") (pin "2") (pinfunction "2_2") (pintype "passive"))
      (node (ref "R81") (pin "2") (pinfunction "2_2") (pintype "passive"))
      (node (ref "R9") (pin "2") (pinfunction "2_2") (pintype "passive"))
      (node (ref "SOLENOID") (pin "2") (pinfunction "2_2") (pintype "passive"))
      (node (ref "SV1") (pin "1") (pinfunction "1_1") (pintype "passive"))
      (node (ref "SV1") (pin "10") (pinfunction "10_10") (pintype "passive"))
      (node (ref "SV1") (pin "12") (pinfunction "12_12") (pintype "passive"))
      (node (ref "SV1") (pin "14") (pinfunction "14_14") (pintype "passive"))
      (node (ref "SV1") (pin "16") (pinfunction "16_16") (pintype "passive"))
      (node (ref "SV1") (pin "18") (pinfunction "18_18") (pintype "passive"))
      (node (ref "SV1") (pin "2") (pinfunction "2_2") (pintype "passive"))
      (node (ref "SV1") (pin "20") (pinfunction "20_20") (pintype "passive"))
      (node (ref "SV1") (pin "3") (pinfunction "3_3") (pintype "passive"))
      (node (ref "SV1") (pin "4") (pinfunction "4_4") (pintype "passive"))
      (node (ref "SV1") (pin "5") (pinfunction "5_5") (pintype "passive"))
      (node (ref "SV1") (pin "6") (pinfunction "6_6") (pintype "passive"))
      (node (ref "SV1") (pin "7") (pinfunction "7_7") (pintype "passive"))
      (node (ref "SV1") (pin "8") (pinfunction "8_8") (pintype "passive"))
      (node (ref "TRIM") (pin "1") (pinfunction "1_1") (pintype "passive"))
      (node (ref "U$5") (pin "3") (pinfunction "4_3") (pintype "bidirectional"))
      (node (ref "U$5") (pin "4") (pinfunction "3_4") (pintype "bidirectional"))
      (node (ref "Z1") (pin "A") (pinfunction "A_A") (pintype "passive"))
      (node (ref "Z2") (pin "A") (pinfunction "A_A") (pintype "passive"))
    )
    (net (code "26") (name "INT") (class "Default")
      (node (ref "OR_6") (pin "6") (pinfunction "Y2_6") (pintype "output"))
      (node (ref "Q1") (pin "3") (pinfunction "D_3") (pintype "passive"))
      (node (ref "R77") (pin "2") (pinfunction "2_2") (pintype "passive"))
    )
    (net (code "27") (name "INT_3V") (class "Default")
      (node (ref "Q1") (pin "2") (pinfunction "S_2") (pintype "passive"))
      (node (ref "R73") (pin "2") (pinfunction "2_2") (pintype "passive"))
      (node (ref "SV1") (pin "32") (pinfunction "32_32") (pintype "passive"))
    )
    (net (code "28") (name "IO0") (class "Default")
      (node (ref "AT28BV25628T") (pin "18") (pinfunction "I/O0_18") (pintype "bidirectional"))
      (node (ref "IC1") (pin "20") (pinfunction "B1_20") (pintype "bidirectional"))
      (node (ref "IO_0") (pin "TP") (pinfunction "TP_TP") (pintype "input"))
      (node (ref "OR_5") (pin "9") (pinfunction "A3_9") (pintype "input"))
    )
    (net (code "29") (name "IO0,1") (class "Default")
      (node (ref "OR_5") (pin "8") (pinfunction "Y3_8") (pintype "output"))
      (node (ref "OR_6") (pin "10") (pinfunction "B3_10") (pintype "input"))
    )
    (net (code "30") (name "IO0,1,2,3") (class "Default")
      (node (ref "OR_6") (pin "5") (pinfunction "B2_5") (pintype "input"))
      (node (ref "OR_6") (pin "8") (pinfunction "Y3_8") (pintype "output"))
    )
    (net (code "31") (name "IO0_3V") (class "Default")
      (node (ref "IC1") (pin "1") (pinfunction "A1_1") (pintype "bidirectional"))
      (node (ref "SV1") (pin "40") (pinfunction "40_40") (pintype "passive"))
    )
    (net (code "32") (name "IO1") (class "Default")
      (node (ref "AT28BV25628T") (pin "19") (pinfunction "I/O1_19") (pintype "bidirectional"))
      (node (ref "IC1") (pin "18") (pinfunction "B2_18") (pintype "bidirectional"))
      (node (ref "IO_1") (pin "TP") (pinfunction "TP_TP") (pintype "input"))
      (node (ref "OR_5") (pin "10") (pinfunction "B3_10") (pintype "input"))
    )
    (net (code "33") (name "IO1_3V") (class "Default")
      (node (ref "IC1") (pin "3") (pinfunction "A2_3") (pintype "bidirectional"))
      (node (ref "SV1") (pin "39") (pinfunction "39_39") (pintype "passive"))
    )
    (net (code "34") (name "IO2") (class "Default")
      (node (ref "AT28BV25628T") (pin "20") (pinfunction "I/O2_20") (pintype "bidirectional"))
      (node (ref "IC1") (pin "17") (pinfunction "B3_17") (pintype "bidirectional"))
      (node (ref "IO_2") (pin "TP") (pinfunction "TP_TP") (pintype "input"))
      (node (ref "OR_5") (pin "1") (pinfunction "A1_1") (pintype "input"))
    )
    (net (code "35") (name "IO2,3") (class "Default")
      (node (ref "OR_5") (pin "3") (pinfunction "Y1_3") (pintype "output"))
      (node (ref "OR_6") (pin "9") (pinfunction "A3_9") (pintype "input"))
    )
    (net (code "36") (name "IO2_3V") (class "Default")
      (node (ref "IC1") (pin "4") (pinfunction "A3_4") (pintype "bidirectional"))
      (node (ref "SV1") (pin "38") (pinfunction "38_38") (pintype "passive"))
    )
    (net (code "37") (name "IO3") (class "Default")
      (node (ref "AT28BV25628T") (pin "22") (pinfunction "I/O3_22") (pintype "bidirectional"))
      (node (ref "IC1") (pin "16") (pinfunction "B4_16") (pintype "bidirectional"))
      (node (ref "IO_3") (pin "TP") (pinfunction "TP_TP") (pintype "input"))
      (node (ref "OR_5") (pin "2") (pinfunction "B1_2") (pintype "input"))
    )
    (net (code "38") (name "IO3_3V") (class "Default")
      (node (ref "IC1") (pin "5") (pinfunction "A4_5") (pintype "bidirectional"))
      (node (ref "SV1") (pin "37") (pinfunction "37_37") (pintype "passive"))
    )
    (net (code "39") (name "IO4") (class "Default")
      (node (ref "AT28BV25628T") (pin "23") (pinfunction "I/O4_23") (pintype "bidirectional"))
      (node (ref "IC1") (pin "15") (pinfunction "B5_15") (pintype "bidirectional"))
      (node (ref "IO_4") (pin "TP") (pinfunction "TP_TP") (pintype "input"))
      (node (ref "OR_5") (pin "4") (pinfunction "A2_4") (pintype "input"))
    )
    (net (code "40") (name "IO4,5") (class "Default")
      (node (ref "OR_5") (pin "6") (pinfunction "Y2_6") (pintype "output"))
      (node (ref "OR_6") (pin "1") (pinfunction "A1_1") (pintype "input"))
    )
    (net (code "41") (name "IO4,5,6,7") (class "Default")
      (node (ref "OR_6") (pin "3") (pinfunction "Y1_3") (pintype "output"))
      (node (ref "OR_6") (pin "4") (pinfunction "A2_4") (pintype "input"))
    )
    (net (code "42") (name "IO4_3V") (class "Default")
      (node (ref "IC1") (pin "6") (pinfunction "A5_6") (pintype "bidirectional"))
      (node (ref "SV1") (pin "36") (pinfunction "36_36") (pintype "passive"))
    )
    (net (code "43") (name "IO5") (class "Default")
      (node (ref "AT28BV25628T") (pin "24") (pinfunction "I/O5_24") (pintype "bidirectional"))
      (node (ref "IC1") (pin "14") (pinfunction "B6_14") (pintype "bidirectional"))
      (node (ref "IO_5") (pin "TP") (pinfunction "TP_TP") (pintype "input"))
      (node (ref "OR_5") (pin "5") (pinfunction "B2_5") (pintype "input"))
    )
    (net (code "44") (name "IO5_3V") (class "Default")
      (node (ref "IC1") (pin "7") (pinfunction "A6_7") (pintype "bidirectional"))
      (node (ref "SV1") (pin "35") (pinfunction "35_35") (pintype "passive"))
    )
    (net (code "45") (name "IO6") (class "Default")
      (node (ref "AT28BV25628T") (pin "25") (pinfunction "I/O6_25") (pintype "bidirectional"))
      (node (ref "IC1") (pin "13") (pinfunction "B7_13") (pintype "bidirectional"))
      (node (ref "IO_6") (pin "TP") (pinfunction "TP_TP") (pintype "input"))
      (node (ref "OR_5") (pin "12") (pinfunction "A4_12") (pintype "input"))
    )
    (net (code "46") (name "IO6,7") (class "Default")
      (node (ref "OR_5") (pin "11") (pinfunction "Y4_11") (pintype "output"))
      (node (ref "OR_6") (pin "2") (pinfunction "B1_2") (pintype "input"))
    )
    (net (code "47") (name "IO6_3V") (class "Default")
      (node (ref "IC1") (pin "8") (pinfunction "A7_8") (pintype "bidirectional"))
      (node (ref "SV1") (pin "34") (pinfunction "34_34") (pintype "passive"))
    )
    (net (code "48") (name "IO7") (class "Default")
      (node (ref "AT28BV25628T") (pin "26") (pinfunction "I/O7_26") (pintype "bidirectional"))
      (node (ref "IC1") (pin "12") (pinfunction "B8_12") (pintype "bidirectional"))
      (node (ref "IO_7") (pin "TP") (pinfunction "TP_TP") (pintype "input"))
      (node (ref "OR_5") (pin "13") (pinfunction "B4_13") (pintype "input"))
    )
    (net (code "49") (name "IO7_3V") (class "Default")
      (node (ref "IC1") (pin "9") (pinfunction "A8_9") (pintype "bidirectional"))
      (node (ref "SV1") (pin "33") (pinfunction "33_33") (pintype "passive"))
    )
    (net (code "50") (name "KICK") (class "Default")
      (node (ref "Q2") (pin "G") (pinfunction "G_G") (pintype "passive"))
      (node (ref "R78") (pin "2") (pinfunction "2_2") (pintype "passive"))
      (node (ref "SV1") (pin "31") (pinfunction "31_31") (pintype "passive"))
    )
    (net (code "51") (name "L1") (class "Default")
      (node (ref "COMP_1") (pin "4") (pinfunction "4_4") (pintype "passive"))
      (node (ref "OR_1") (pin "1") (pinfunction "A1_1") (pintype "input"))
    )
    (net (code "52") (name "L2") (class "Default")
      (node (ref "COMP_2") (pin "4") (pinfunction "4_4") (pintype "passive"))
      (node (ref "OR_1") (pin "2") (pinfunction "B1_2") (pintype "input"))
    )
    (net (code "53") (name "L3") (class "Default")
      (node (ref "COMP_3") (pin "4") (pinfunction "4_4") (pintype "passive"))
      (node (ref "OR_1") (pin "4") (pinfunction "A2_4") (pintype "input"))
    )
    (net (code "54") (name "L4") (class "Default")
      (node (ref "COMP_4") (pin "4") (pinfunction "4_4") (pintype "passive"))
      (node (ref "OR_1") (pin "5") (pinfunction "B2_5") (pintype "input"))
    )
    (net (code "55") (name "L5") (class "Default")
      (node (ref "COMP_5") (pin "4") (pinfunction "4_4") (pintype "passive"))
      (node (ref "OR_1") (pin "9") (pinfunction "A3_9") (pintype "input"))
    )
    (net (code "56") (name "L6") (class "Default")
      (node (ref "COMP_6") (pin "4") (pinfunction "4_4") (pintype "passive"))
      (node (ref "OR_1") (pin "10") (pinfunction "B3_10") (pintype "input"))
    )
    (net (code "57") (name "L7") (class "Default")
      (node (ref "COMP_7") (pin "4") (pinfunction "4_4") (pintype "passive"))
      (node (ref "OR_1") (pin "12") (pinfunction "A4_12") (pintype "input"))
    )
    (net (code "58") (name "L8") (class "Default")
      (node (ref "COMP_8") (pin "4") (pinfunction "4_4") (pintype "passive"))
      (node (ref "OR_1") (pin "13") (pinfunction "B4_13") (pintype "input"))
    )
    (net (code "59") (name "L9") (class "Default")
      (node (ref "COMP_9") (pin "4") (pinfunction "4_4") (pintype "passive"))
      (node (ref "OR_2") (pin "1") (pinfunction "A1_1") (pintype "input"))
    )
    (net (code "60") (name "L10") (class "Default")
      (node (ref "COMP_10") (pin "4") (pinfunction "4_4") (pintype "passive"))
      (node (ref "OR_2") (pin "2") (pinfunction "B1_2") (pintype "input"))
    )
    (net (code "61") (name "L11") (class "Default")
      (node (ref "COMP_11") (pin "4") (pinfunction "4_4") (pintype "passive"))
      (node (ref "OR_2") (pin "4") (pinfunction "A2_4") (pintype "input"))
    )
    (net (code "62") (name "L12") (class "Default")
      (node (ref "COMP_12") (pin "4") (pinfunction "4_4") (pintype "passive"))
      (node (ref "OR_2") (pin "5") (pinfunction "B2_5") (pintype "input"))
    )
    (net (code "63") (name "L13") (class "Default")
      (node (ref "COMP_13") (pin "4") (pinfunction "4_4") (pintype "passive"))
      (node (ref "OR_2") (pin "9") (pinfunction "A3_9") (pintype "input"))
    )
    (net (code "64") (name "L14") (class "Default")
      (node (ref "COMP_14") (pin "4") (pinfunction "4_4") (pintype "passive"))
      (node (ref "OR_2") (pin "10") (pinfunction "B3_10") (pintype "input"))
    )
    (net (code "65") (name "L15") (class "Default")
      (node (ref "COMP_15") (pin "4") (pinfunction "4_4") (pintype "passive"))
      (node (ref "OR_2") (pin "12") (pinfunction "A4_12") (pintype "input"))
    )
    (net (code "66") (name "L16") (class "Default")
      (node (ref "COMP_16") (pin "4") (pinfunction "4_4") (pintype "passive"))
      (node (ref "OR_2") (pin "13") (pinfunction "B4_13") (pintype "input"))
    )
    (net (code "67") (name "L17") (class "Default")
      (node (ref "COMP_17") (pin "4") (pinfunction "4_4") (pintype "passive"))
      (node (ref "OR_3") (pin "1") (pinfunction "A1_1") (pintype "input"))
    )
    (net (code "68") (name "L18") (class "Default")
      (node (ref "COMP_18") (pin "4") (pinfunction "4_4") (pintype "passive"))
      (node (ref "OR_3") (pin "2") (pinfunction "B1_2") (pintype "input"))
    )
    (net (code "69") (name "L19") (class "Default")
      (node (ref "COMP_19") (pin "4") (pinfunction "4_4") (pintype "passive"))
      (node (ref "OR_3") (pin "4") (pinfunction "A2_4") (pintype "input"))
    )
    (net (code "70") (name "L20") (class "Default")
      (node (ref "COMP_20") (pin "4") (pinfunction "4_4") (pintype "passive"))
      (node (ref "OR_3") (pin "5") (pinfunction "B2_5") (pintype "input"))
    )
    (net (code "71") (name "L21") (class "Default")
      (node (ref "COMP_21") (pin "4") (pinfunction "4_4") (pintype "passive"))
      (node (ref "OR_3") (pin "9") (pinfunction "A3_9") (pintype "input"))
    )
    (net (code "72") (name "L22") (class "Default")
      (node (ref "COMP_22") (pin "4") (pinfunction "4_4") (pintype "passive"))
      (node (ref "OR_3") (pin "10") (pinfunction "B3_10") (pintype "input"))
    )
    (net (code "73") (name "L23") (class "Default")
      (node (ref "COMP_23") (pin "4") (pinfunction "4_4") (pintype "passive"))
      (node (ref "OR_3") (pin "12") (pinfunction "A4_12") (pintype "input"))
    )
    (net (code "74") (name "L24") (class "Default")
      (node (ref "COMP_24") (pin "4") (pinfunction "4_4") (pintype "passive"))
      (node (ref "OR_3") (pin "13") (pinfunction "B4_13") (pintype "input"))
    )
    (net (code "75") (name "L25") (class "Default")
      (node (ref "COMP_25") (pin "4") (pinfunction "4_4") (pintype "passive"))
      (node (ref "OR_4") (pin "1") (pinfunction "A1_1") (pintype "input"))
    )
    (net (code "76") (name "L26") (class "Default")
      (node (ref "COMP_26") (pin "4") (pinfunction "4_4") (pintype "passive"))
      (node (ref "OR_4") (pin "2") (pinfunction "B1_2") (pintype "input"))
    )
    (net (code "77") (name "L27") (class "Default")
      (node (ref "COMP_27") (pin "4") (pinfunction "4_4") (pintype "passive"))
      (node (ref "OR_4") (pin "4") (pinfunction "A2_4") (pintype "input"))
    )
    (net (code "78") (name "L28") (class "Default")
      (node (ref "COMP_28") (pin "4") (pinfunction "4_4") (pintype "passive"))
      (node (ref "OR_4") (pin "5") (pinfunction "B2_5") (pintype "input"))
    )
    (net (code "79") (name "L29") (class "Default")
      (node (ref "COMP_29") (pin "4") (pinfunction "4_4") (pintype "passive"))
      (node (ref "OR_4") (pin "9") (pinfunction "A3_9") (pintype "input"))
    )
    (net (code "80") (name "L30") (class "Default")
      (node (ref "COMP_30") (pin "4") (pinfunction "4_4") (pintype "passive"))
      (node (ref "OR_4") (pin "10") (pinfunction "B3_10") (pintype "input"))
    )
    (net (code "81") (name "Net-(C49-Pad+)") (class "Default")
      (node (ref "C49") (pin "+") (pinfunction "+_+") (pintype "passive"))
      (node (ref "C50") (pin "+") (pinfunction "+_+") (pintype "passive"))
      (node (ref "Q2") (pin "D") (pinfunction "D_D") (pintype "passive"))
      (node (ref "Q3") (pin "S") (pinfunction "S_S") (pintype "passive"))
      (node (ref "R80") (pin "1") (pinfunction "1_1") (pintype "passive"))
    )
    (net (code "82") (name "Net-(FUSE-Pad2)") (class "Default")
      (node (ref "FUSE") (pin "2") (pinfunction "2_2") (pintype "passive"))
      (node (ref "FUSE1") (pin "2") (pinfunction "2_2") (pintype "passive"))
      (node (ref "FUSE2") (pin "2") (pinfunction "2_2") (pintype "passive"))
      (node (ref "U$4") (pin "1") (pinfunction "1_1") (pintype "bidirectional"))
      (node (ref "U$4") (pin "2") (pinfunction "2_2") (pintype "bidirectional"))
    )
    (net (code "83") (name "Net-(IO1-OUT)") (class "Default")
      (node (ref "IO1") (pin "2") (pinfunction "OUT_2") (pintype "output"))
      (node (ref "L1") (pin "1") (pinfunction "1_1") (pintype "passive"))
      (node (ref "Z2") (pin "C") (pinfunction "C_C") (pintype "passive"))
    )
    (net (code "84") (name "Net-(IO2-OUT)") (class "Default")
      (node (ref "IO2") (pin "2") (pinfunction "OUT_2") (pintype "output"))
      (node (ref "L2") (pin "1") (pinfunction "1_1") (pintype "passive"))
      (node (ref "Z1") (pin "C") (pinfunction "C_C") (pintype "passive"))
    )
    (net (code "85") (name "Net-(MAIN_POWER-2-COM)") (class "Default")
      (node (ref "FUSE") (pin "1") (pinfunction "1_1") (pintype "passive"))
      (node (ref "MAIN_POWER") (pin "2") (pinfunction "2-COM_2") (pintype "passive"))
    )
    (net (code "86") (name "Net-(Q2-PadS)") (class "Default")
      (node (ref "Q2") (pin "S") (pinfunction "S_S") (pintype "passive"))
      (node (ref "SOLENOID") (pin "1") (pinfunction "1_1") (pintype "passive"))
    )
    (net (code "87") (name "Net-(TCRT_1-CATHODE)") (class "Default")
      (node (ref "R1") (pin "1") (pinfunction "1_1") (pintype "passive"))
      (node (ref "TCRT_1") (pin "K") (pinfunction "CATHODE_K") (pintype "passive"))
    )
    (net (code "88") (name "Net-(TCRT_1-EMITTER)") (class "Default")
      (node (ref "1") (pin "TP") (pinfunction "TP_TP") (pintype "input"))
      (node (ref "COMP_1") (pin "3") (pinfunction "3_3") (pintype "passive"))
      (node (ref "R2") (pin "1") (pinfunction "1_1") (pintype "passive"))
      (node (ref "TCRT_1") (pin "E") (pinfunction "EMITTER_E") (pintype "passive"))
    )
    (net (code "89") (name "Net-(TCRT_2-CATHODE)") (class "Default")
      (node (ref "R3") (pin "1") (pinfunction "1_1") (pintype "passive"))
      (node (ref "TCRT_2") (pin "K") (pinfunction "CATHODE_K") (pintype "passive"))
    )
    (net (code "90") (name "Net-(TCRT_2-EMITTER)") (class "Default")
      (node (ref "2") (pin "TP") (pinfunction "TP_TP") (pintype "input"))
      (node (ref "COMP_2") (pin "3") (pinfunction "3_3") (pintype "passive"))
      (node (ref "R4") (pin "1") (pinfunction "1_1") (pintype "passive"))
      (node (ref "TCRT_2") (pin "E") (pinfunction "EMITTER_E") (pintype "passive"))
    )
    (net (code "91") (name "Net-(TCRT_3-CATHODE)") (class "Default")
      (node (ref "R5") (pin "1") (pinfunction "1_1") (pintype "passive"))
      (node (ref "TCRT_3") (pin "K") (pinfunction "CATHODE_K") (pintype "passive"))
    )
    (net (code "92") (name "Net-(TCRT_3-EMITTER)") (class "Default")
      (node (ref "3") (pin "TP") (pinfunction "TP_TP") (pintype "input"))
      (node (ref "COMP_3") (pin "3") (pinfunction "3_3") (pintype "passive"))
      (node (ref "R6") (pin "1") (pinfunction "1_1") (pintype "passive"))
      (node (ref "TCRT_3") (pin "E") (pinfunction "EMITTER_E") (pintype "passive"))
    )
    (net (code "93") (name "Net-(TCRT_4-CATHODE)") (class "Default")
      (node (ref "R7") (pin "1") (pinfunction "1_1") (pintype "passive"))
      (node (ref "TCRT_4") (pin "K") (pinfunction "CATHODE_K") (pintype "passive"))
    )
    (net (code "94") (name "Net-(TCRT_4-EMITTER)") (class "Default")
      (node (ref "4") (pin "TP") (pinfunction "TP_TP") (pintype "input"))
      (node (ref "COMP_4") (pin "3") (pinfunction "3_3") (pintype "passive"))
      (node (ref "R8") (pin "1") (pinfunction "1_1") (pintype "passive"))
      (node (ref "TCRT_4") (pin "E") (pinfunction "EMITTER_E") (pintype "passive"))
    )
    (net (code "95") (name "Net-(TCRT_5-CATHODE)") (class "Default")
      (node (ref "R9") (pin "1") (pinfunction "1_1") (pintype "passive"))
      (node (ref "TCRT_5") (pin "K") (pinfunction "CATHODE_K") (pintype "passive"))
    )
    (net (code "96") (name "Net-(TCRT_5-EMITTER)") (class "Default")
      (node (ref "5") (pin "TP") (pinfunction "TP_TP") (pintype "input"))
      (node (ref "COMP_5") (pin "3") (pinfunction "3_3") (pintype "passive"))
      (node (ref "R10") (pin "1") (pinfunction "1_1") (pintype "passive"))
      (node (ref "TCRT_5") (pin "E") (pinfunction "EMITTER_E") (pintype "passive"))
    )
    (net (code "97") (name "Net-(TCRT_6-CATHODE)") (class "Default")
      (node (ref "R11") (pin "1") (pinfunction "1_1") (pintype "passive"))
      (node (ref "TCRT_6") (pin "K") (pinfunction "CATHODE_K") (pintype "passive"))
    )
    (net (code "98") (name "Net-(TCRT_6-EMITTER)") (class "Default")
      (node (ref "6") (pin "TP") (pinfunction "TP_TP") (pintype "input"))
      (node (ref "COMP_6") (pin "3") (pinfunction "3_3") (pintype "passive"))
      (node (ref "R12") (pin "1") (pinfunction "1_1") (pintype "passive"))
      (node (ref "TCRT_6") (pin "E") (pinfunction "EMITTER_E") (pintype "passive"))
    )
    (net (code "99") (name "Net-(TCRT_7-CATHODE)") (class "Default")
      (node (ref "R13") (pin "1") (pinfunction "1_1") (pintype "passive"))
      (node (ref "TCRT_7") (pin "K") (pinfunction "CATHODE_K") (pintype "passive"))
    )
    (net (code "100") (name "Net-(TCRT_7-EMITTER)") (class "Default")
      (node (ref "7") (pin "TP") (pinfunction "TP_TP") (pintype "input"))
      (node (ref "COMP_7") (pin "3") (pinfunction "3_3") (pintype "passive"))
      (node (ref "R14") (pin "1") (pinfunction "1_1") (pintype "passive"))
      (node (ref "TCRT_7") (pin "E") (pinfunction "EMITTER_E") (pintype "passive"))
    )
    (net (code "101") (name "Net-(TCRT_8-CATHODE)") (class "Default")
      (node (ref "R15") (pin "1") (pinfunction "1_1") (pintype "passive"))
      (node (ref "TCRT_8") (pin "K") (pinfunction "CATHODE_K") (pintype "passive"))
    )
    (net (code "102") (name "Net-(TCRT_8-EMITTER)") (class "Default")
      (node (ref "8") (pin "TP") (pinfunction "TP_TP") (pintype "input"))
      (node (ref "COMP_8") (pin "3") (pinfunction "3_3") (pintype "passive"))
      (node (ref "R16") (pin "1") (pinfunction "1_1") (pintype "passive"))
      (node (ref "TCRT_8") (pin "E") (pinfunction "EMITTER_E") (pintype "passive"))
    )
    (net (code "103") (name "Net-(TCRT_9-CATHODE)") (class "Default")
      (node (ref "R17") (pin "1") (pinfunction "1_1") (pintype "passive"))
      (node (ref "TCRT_9") (pin "K") (pinfunction "CATHODE_K") (pintype "passive"))
    )
    (net (code "104") (name "Net-(TCRT_9-EMITTER)") (class "Default")
      (node (ref "9") (pin "TP") (pinfunction "TP_TP") (pintype "input"))
      (node (ref "COMP_9") (pin "3") (pinfunction "3_3") (pintype "passive"))
      (node (ref "R18") (pin "1") (pinfunction "1_1") (pintype "passive"))
      (node (ref "TCRT_9") (pin "E") (pinfunction "EMITTER_E") (pintype "passive"))
    )
    (net (code "105") (name "Net-(TCRT_10-CATHODE)") (class "Default")
      (node (ref "R19") (pin "1") (pinfunction "1_1") (pintype "passive"))
      (node (ref "TCRT_10") (pin "K") (pinfunction "CATHODE_K") (pintype "passive"))
    )
    (net (code "106") (name "Net-(TCRT_10-EMITTER)") (class "Default")
      (node (ref "10") (pin "TP") (pinfunction "TP_TP") (pintype "input"))
      (node (ref "COMP_10") (pin "3") (pinfunction "3_3") (pintype "passive"))
      (node (ref "R20") (pin "1") (pinfunction "1_1") (pintype "passive"))
      (node (ref "TCRT_10") (pin "E") (pinfunction "EMITTER_E") (pintype "passive"))
    )
    (net (code "107") (name "Net-(TCRT_11-CATHODE)") (class "Default")
      (node (ref "R21") (pin "1") (pinfunction "1_1") (pintype "passive"))
      (node (ref "TCRT_11") (pin "K") (pinfunction "CATHODE_K") (pintype "passive"))
    )
    (net (code "108") (name "Net-(TCRT_11-EMITTER)") (class "Default")
      (node (ref "11") (pin "TP") (pinfunction "TP_TP") (pintype "input"))
      (node (ref "COMP_11") (pin "3") (pinfunction "3_3") (pintype "passive"))
      (node (ref "R22") (pin "1") (pinfunction "1_1") (pintype "passive"))
      (node (ref "TCRT_11") (pin "E") (pinfunction "EMITTER_E") (pintype "passive"))
    )
    (net (code "109") (name "Net-(TCRT_12-CATHODE)") (class "Default")
      (node (ref "R23") (pin "1") (pinfunction "1_1") (pintype "passive"))
      (node (ref "TCRT_12") (pin "K") (pinfunction "CATHODE_K") (pintype "passive"))
    )
    (net (code "110") (name "Net-(TCRT_12-EMITTER)") (class "Default")
      (node (ref "12") (pin "TP") (pinfunction "TP_TP") (pintype "input"))
      (node (ref "COMP_12") (pin "3") (pinfunction "3_3") (pintype "passive"))
      (node (ref "R24") (pin "1") (pinfunction "1_1") (pintype "passive"))
      (node (ref "TCRT_12") (pin "E") (pinfunction "EMITTER_E") (pintype "passive"))
    )
    (net (code "111") (name "Net-(TCRT_13-CATHODE)") (class "Default")
      (node (ref "R25") (pin "1") (pinfunction "1_1") (pintype "passive"))
      (node (ref "TCRT_13") (pin "K") (pinfunction "CATHODE_K") (pintype "passive"))
    )
    (net (code "112") (name "Net-(TCRT_13-EMITTER)") (class "Default")
      (node (ref "13") (pin "TP") (pinfunction "TP_TP") (pintype "input"))
      (node (ref "COMP_13") (pin "3") (pinfunction "3_3") (pintype "passive"))
      (node (ref "R26") (pin "1") (pinfunction "1_1") (pintype "passive"))
      (node (ref "TCRT_13") (pin "E") (pinfunction "EMITTER_E") (pintype "passive"))
    )
    (net (code "113") (name "Net-(TCRT_14-CATHODE)") (class "Default")
      (node (ref "R27") (pin "1") (pinfunction "1_1") (pintype "passive"))
      (node (ref "TCRT_14") (pin "K") (pinfunction "CATHODE_K") (pintype "passive"))
    )
    (net (code "114") (name "Net-(TCRT_14-EMITTER)") (class "Default")
      (node (ref "14") (pin "TP") (pinfunction "TP_TP") (pintype "input"))
      (node (ref "COMP_14") (pin "3") (pinfunction "3_3") (pintype "passive"))
      (node (ref "R28") (pin "1") (pinfunction "1_1") (pintype "passive"))
      (node (ref "TCRT_14") (pin "E") (pinfunction "EMITTER_E") (pintype "passive"))
    )
    (net (code "115") (name "Net-(TCRT_15-CATHODE)") (class "Default")
      (node (ref "R29") (pin "1") (pinfunction "1_1") (pintype "passive"))
      (node (ref "TCRT_15") (pin "K") (pinfunction "CATHODE_K") (pintype "passive"))
    )
    (net (code "116") (name "Net-(TCRT_15-EMITTER)") (class "Default")
      (node (ref "15") (pin "TP") (pinfunction "TP_TP") (pintype "input"))
      (node (ref "COMP_15") (pin "3") (pinfunction "3_3") (pintype "passive"))
      (node (ref "R30") (pin "1") (pinfunction "1_1") (pintype "passive"))
      (node (ref "TCRT_15") (pin "E") (pinfunction "EMITTER_E") (pintype "passive"))
    )
    (net (code "117") (name "Net-(TCRT_16-CATHODE)") (class "Default")
      (node (ref "R31") (pin "1") (pinfunction "1_1") (pintype "passive"))
      (node (ref "TCRT_16") (pin "K") (pinfunction "CATHODE_K") (pintype "passive"))
    )
    (net (code "118") (name "Net-(TCRT_16-EMITTER)") (class "Default")
      (node (ref "16") (pin "TP") (pinfunction "TP_TP") (pintype "input"))
      (node (ref "COMP_16") (pin "3") (pinfunction "3_3") (pintype "passive"))
      (node (ref "R32") (pin "1") (pinfunction "1_1") (pintype "passive"))
      (node (ref "TCRT_16") (pin "E") (pinfunction "EMITTER_E") (pintype "passive"))
    )
    (net (code "119") (name "Net-(TCRT_17-CATHODE)") (class "Default")
      (node (ref "R33") (pin "1") (pinfunction "1_1") (pintype "passive"))
      (node (ref "TCRT_17") (pin "K") (pinfunction "CATHODE_K") (pintype "passive"))
    )
    (net (code "120") (name "Net-(TCRT_17-EMITTER)") (class "Default")
      (node (ref "17") (pin "TP") (pinfunction "TP_TP") (pintype "input"))
      (node (ref "COMP_17") (pin "3") (pinfunction "3_3") (pintype "passive"))
      (node (ref "R34") (pin "1") (pinfunction "1_1") (pintype "passive"))
      (node (ref "TCRT_17") (pin "E") (pinfunction "EMITTER_E") (pintype "passive"))
    )
    (net (code "121") (name "Net-(TCRT_18-CATHODE)") (class "Default")
      (node (ref "R35") (pin "1") (pinfunction "1_1") (pintype "passive"))
      (node (ref "TCRT_18") (pin "K") (pinfunction "CATHODE_K") (pintype "passive"))
    )
    (net (code "122") (name "Net-(TCRT_18-EMITTER)") (class "Default")
      (node (ref "18") (pin "TP") (pinfunction "TP_TP") (pintype "input"))
      (node (ref "COMP_18") (pin "3") (pinfunction "3_3") (pintype "passive"))
      (node (ref "R36") (pin "1") (pinfunction "1_1") (pintype "passive"))
      (node (ref "TCRT_18") (pin "E") (pinfunction "EMITTER_E") (pintype "passive"))
    )
    (net (code "123") (name "Net-(TCRT_19-CATHODE)") (class "Default")
      (node (ref "R37") (pin "1") (pinfunction "1_1") (pintype "passive"))
      (node (ref "TCRT_19") (pin "K") (pinfunction "CATHODE_K") (pintype "passive"))
    )
    (net (code "124") (name "Net-(TCRT_19-EMITTER)") (class "Default")
      (node (ref "19") (pin "TP") (pinfunction "TP_TP") (pintype "input"))
      (node (ref "COMP_19") (pin "3") (pinfunction "3_3") (pintype "passive"))
      (node (ref "R38") (pin "1") (pinfunction "1_1") (pintype "passive"))
      (node (ref "TCRT_19") (pin "E") (pinfunction "EMITTER_E") (pintype "passive"))
    )
    (net (code "125") (name "Net-(TCRT_20-CATHODE)") (class "Default")
      (node (ref "R39") (pin "1") (pinfunction "1_1") (pintype "passive"))
      (node (ref "TCRT_20") (pin "K") (pinfunction "CATHODE_K") (pintype "passive"))
    )
    (net (code "126") (name "Net-(TCRT_20-EMITTER)") (class "Default")
      (node (ref "20") (pin "TP") (pinfunction "TP_TP") (pintype "input"))
      (node (ref "COMP_20") (pin "3") (pinfunction "3_3") (pintype "passive"))
      (node (ref "R40") (pin "1") (pinfunction "1_1") (pintype "passive"))
      (node (ref "TCRT_20") (pin "E") (pinfunction "EMITTER_E") (pintype "passive"))
    )
    (net (code "127") (name "Net-(TCRT_21-CATHODE)") (class "Default")
      (node (ref "R41") (pin "1") (pinfunction "1_1") (pintype "passive"))
      (node (ref "TCRT_21") (pin "K") (pinfunction "CATHODE_K") (pintype "passive"))
    )
    (net (code "128") (name "Net-(TCRT_21-EMITTER)") (class "Default")
      (node (ref "21") (pin "TP") (pinfunction "TP_TP") (pintype "input"))
      (node (ref "COMP_21") (pin "3") (pinfunction "3_3") (pintype "passive"))
      (node (ref "R42") (pin "1") (pinfunction "1_1") (pintype "passive"))
      (node (ref "TCRT_21") (pin "E") (pinfunction "EMITTER_E") (pintype "passive"))
    )
    (net (code "129") (name "Net-(TCRT_22-CATHODE)") (class "Default")
      (node (ref "R43") (pin "1") (pinfunction "1_1") (pintype "passive"))
      (node (ref "TCRT_22") (pin "K") (pinfunction "CATHODE_K") (pintype "passive"))
    )
    (net (code "130") (name "Net-(TCRT_22-EMITTER)") (class "Default")
      (node (ref "22") (pin "TP") (pinfunction "TP_TP") (pintype "input"))
      (node (ref "COMP_22") (pin "3") (pinfunction "3_3") (pintype "passive"))
      (node (ref "R44") (pin "1") (pinfunction "1_1") (pintype "passive"))
      (node (ref "TCRT_22") (pin "E") (pinfunction "EMITTER_E") (pintype "passive"))
    )
    (net (code "131") (name "Net-(TCRT_23-CATHODE)") (class "Default")
      (node (ref "R45") (pin "1") (pinfunction "1_1") (pintype "passive"))
      (node (ref "TCRT_23") (pin "K") (pinfunction "CATHODE_K") (pintype "passive"))
    )
    (net (code "132") (name "Net-(TCRT_23-EMITTER)") (class "Default")
      (node (ref "23") (pin "TP") (pinfunction "TP_TP") (pintype "input"))
      (node (ref "COMP_23") (pin "3") (pinfunction "3_3") (pintype "passive"))
      (node (ref "R46") (pin "1") (pinfunction "1_1") (pintype "passive"))
      (node (ref "TCRT_23") (pin "E") (pinfunction "EMITTER_E") (pintype "passive"))
    )
    (net (code "133") (name "Net-(TCRT_24-CATHODE)") (class "Default")
      (node (ref "R47") (pin "1") (pinfunction "1_1") (pintype "passive"))
      (node (ref "TCRT_24") (pin "K") (pinfunction "CATHODE_K") (pintype "passive"))
    )
    (net (code "134") (name "Net-(TCRT_24-EMITTER)") (class "Default")
      (node (ref "24") (pin "TP") (pinfunction "TP_TP") (pintype "input"))
      (node (ref "COMP_24") (pin "3") (pinfunction "3_3") (pintype "passive"))
      (node (ref "R48") (pin "1") (pinfunction "1_1") (pintype "passive"))
      (node (ref "TCRT_24") (pin "E") (pinfunction "EMITTER_E") (pintype "passive"))
    )
    (net (code "135") (name "Net-(TCRT_25-CATHODE)") (class "Default")
      (node (ref "R49") (pin "1") (pinfunction "1_1") (pintype "passive"))
      (node (ref "TCRT_25") (pin "K") (pinfunction "CATHODE_K") (pintype "passive"))
    )
    (net (code "136") (name "Net-(TCRT_25-EMITTER)") (class "Default")
      (node (ref "25") (pin "TP") (pinfunction "TP_TP") (pintype "input"))
      (node (ref "COMP_25") (pin "3") (pinfunction "3_3") (pintype "passive"))
      (node (ref "R50") (pin "1") (pinfunction "1_1") (pintype "passive"))
      (node (ref "TCRT_25") (pin "E") (pinfunction "EMITTER_E") (pintype "passive"))
    )
    (net (code "137") (name "Net-(TCRT_26-CATHODE)") (class "Default")
      (node (ref "R51") (pin "1") (pinfunction "1_1") (pintype "passive"))
      (node (ref "TCRT_26") (pin "K") (pinfunction "CATHODE_K") (pintype "passive"))
    )
    (net (code "138") (name "Net-(TCRT_26-EMITTER)") (class "Default")
      (node (ref "26") (pin "TP") (pinfunction "TP_TP") (pintype "input"))
      (node (ref "COMP_26") (pin "3") (pinfunction "3_3") (pintype "passive"))
      (node (ref "R52") (pin "1") (pinfunction "1_1") (pintype "passive"))
      (node (ref "TCRT_26") (pin "E") (pinfunction "EMITTER_E") (pintype "passive"))
    )
    (net (code "139") (name "Net-(TCRT_27-CATHODE)") (class "Default")
      (node (ref "R53") (pin "1") (pinfunction "1_1") (pintype "passive"))
      (node (ref "TCRT_27") (pin "K") (pinfunction "CATHODE_K") (pintype "passive"))
    )
    (net (code "140") (name "Net-(TCRT_27-EMITTER)") (class "Default")
      (node (ref "27") (pin "TP") (pinfunction "TP_TP") (pintype "input"))
      (node (ref "COMP_27") (pin "3") (pinfunction "3_3") (pintype "passive"))
      (node (ref "R54") (pin "1") (pinfunction "1_1") (pintype "passive"))
      (node (ref "TCRT_27") (pin "E") (pinfunction "EMITTER_E") (pintype "passive"))
    )
    (net (code "141") (name "Net-(TCRT_28-CATHODE)") (class "Default")
      (node (ref "R55") (pin "1") (pinfunction "1_1") (pintype "passive"))
      (node (ref "TCRT_28") (pin "K") (pinfunction "CATHODE_K") (pintype "passive"))
    )
    (net (code "142") (name "Net-(TCRT_28-EMITTER)") (class "Default")
      (node (ref "28") (pin "TP") (pinfunction "TP_TP") (pintype "input"))
      (node (ref "COMP_28") (pin "3") (pinfunction "3_3") (pintype "passive"))
      (node (ref "R56") (pin "1") (pinfunction "1_1") (pintype "passive"))
      (node (ref "TCRT_28") (pin "E") (pinfunction "EMITTER_E") (pintype "passive"))
    )
    (net (code "143") (name "Net-(TCRT_29-CATHODE)") (class "Default")
      (node (ref "R57") (pin "1") (pinfunction "1_1") (pintype "passive"))
      (node (ref "TCRT_29") (pin "K") (pinfunction "CATHODE_K") (pintype "passive"))
    )
    (net (code "144") (name "Net-(TCRT_29-EMITTER)") (class "Default")
      (node (ref "29") (pin "TP") (pinfunction "TP_TP") (pintype "input"))
      (node (ref "COMP_29") (pin "3") (pinfunction "3_3") (pintype "passive"))
      (node (ref "R58") (pin "1") (pinfunction "1_1") (pintype "passive"))
      (node (ref "TCRT_29") (pin "E") (pinfunction "EMITTER_E") (pintype "passive"))
    )
    (net (code "145") (name "Net-(TCRT_30-CATHODE)") (class "Default")
      (node (ref "R59") (pin "1") (pinfunction "1_1") (pintype "passive"))
      (node (ref "TCRT_30") (pin "K") (pinfunction "CATHODE_K") (pintype "passive"))
    )
    (net (code "146") (name "Net-(TCRT_30-EMITTER)") (class "Default")
      (node (ref "30") (pin "TP") (pinfunction "TP_TP") (pintype "input"))
      (node (ref "COMP_30") (pin "3") (pinfunction "3_3") (pintype "passive"))
      (node (ref "R60") (pin "1") (pinfunction "1_1") (pintype "passive"))
      (node (ref "TCRT_30") (pin "E") (pinfunction "EMITTER_E") (pintype "passive"))
    )
    (net (code "147") (name "Net-(U$4-3)") (class "Default")
      (node (ref "U$4") (pin "3") (pinfunction "4_3") (pintype "bidirectional"))
      (node (ref "U$4") (pin "4") (pinfunction "3_4") (pintype "bidirectional"))
      (node (ref "U$5") (pin "1") (pinfunction "1_1") (pintype "bidirectional"))
      (node (ref "U$5") (pin "2") (pinfunction "2_2") (pintype "bidirectional"))
    )
    (net (code "148") (name "REF") (class "Default")
      (node (ref "C52") (pin "2") (pinfunction "2_2") (pintype "passive"))
      (node (ref "COMP_1") (pin "1") (pinfunction "1_1") (pintype "passive"))
      (node (ref "COMP_10") (pin "1") (pinfunction "1_1") (pintype "passive"))
      (node (ref "COMP_11") (pin "1") (pinfunction "1_1") (pintype "passive"))
      (node (ref "COMP_12") (pin "1") (pinfunction "1_1") (pintype "passive"))
      (node (ref "COMP_13") (pin "1") (pinfunction "1_1") (pintype "passive"))
      (node (ref "COMP_14") (pin "1") (pinfunction "1_1") (pintype "passive"))
      (node (ref "COMP_15") (pin "1") (pinfunction "1_1") (pintype "passive"))
      (node (ref "COMP_16") (pin "1") (pinfunction "1_1") (pintype "passive"))
      (node (ref "COMP_17") (pin "1") (pinfunction "1_1") (pintype "passive"))
      (node (ref "COMP_18") (pin "1") (pinfunction "1_1") (pintype "passive"))
      (node (ref "COMP_19") (pin "1") (pinfunction "1_1") (pintype "passive"))
      (node (ref "COMP_2") (pin "1") (pinfunction "1_1") (pintype "passive"))
      (node (ref "COMP_20") (pin "1") (pinfunction "1_1") (pintype "passive"))
      (node (ref "COMP_21") (pin "1") (pinfunction "1_1") (pintype "passive"))
      (node (ref "COMP_22") (pin "1") (pinfunction "1_1") (pintype "passive"))
      (node (ref "COMP_23") (pin "1") (pinfunction "1_1") (pintype "passive"))
      (node (ref "COMP_24") (pin "1") (pinfunction "1_1") (pintype "passive"))
      (node (ref "COMP_25") (pin "1") (pinfunction "1_1") (pintype "passive"))
      (node (ref "COMP_26") (pin "1") (pinfunction "1_1") (pintype "passive"))
      (node (ref "COMP_27") (pin "1") (pinfunction "1_1") (pintype "passive"))
      (node (ref "COMP_28") (pin "1") (pinfunction "1_1") (pintype "passive"))
      (node (ref "COMP_29") (pin "1") (pinfunction "1_1") (pintype "passive"))
      (node (ref "COMP_3") (pin "1") (pinfunction "1_1") (pintype "passive"))
      (node (ref "COMP_30") (pin "1") (pinfunction "1_1") (pintype "passive"))
      (node (ref "COMP_4") (pin "1") (pinfunction "1_1") (pintype "passive"))
      (node (ref "COMP_5") (pin "1") (pinfunction "1_1") (pintype "passive"))
      (node (ref "COMP_6") (pin "1") (pinfunction "1_1") (pintype "passive"))
      (node (ref "COMP_7") (pin "1") (pinfunction "1_1") (pintype "passive"))
      (node (ref "COMP_8") (pin "1") (pinfunction "1_1") (pintype "passive"))
      (node (ref "COMP_9") (pin "1") (pinfunction "1_1") (pintype "passive"))
      (node (ref "TRIM") (pin "2") (pinfunction "2_2") (pintype "passive"))
    )
    (net (code "149") (name "SOLENOID") (class "Default")
      (node (ref "FUSE2") (pin "1") (pinfunction "1_1") (pintype "passive"))
      (node (ref "Q3") (pin "D") (pinfunction "D_D") (pintype "passive"))
    )
    (net (code "150") (name "V_CAP") (class "Default")
      (node (ref "R80") (pin "2") (pinfunction "2_2") (pintype "passive"))
      (node (ref "R81") (pin "1") (pinfunction "1_1") (pintype "passive"))
      (node (ref "SV1") (pin "29") (pinfunction "29_29") (pintype "passive"))
    )
    (net (code "151") (name "Y1") (class "Default")
      (node (ref "OR_1") (pin "3") (pinfunction "Y1_3") (pintype "output"))
      (node (ref "R63") (pin "2") (pinfunction "2_2") (pintype "passive"))
    )
    (net (code "152") (name "Y2") (class "Default")
      (node (ref "OR_1") (pin "6") (pinfunction "Y2_6") (pintype "output"))
      (node (ref "R64") (pin "2") (pinfunction "2_2") (pintype "passive"))
    )
    (net (code "153") (name "Y3") (class "Default")
      (node (ref "OR_1") (pin "8") (pinfunction "Y3_8") (pintype "output"))
      (node (ref "R62") (pin "2") (pinfunction "2_2") (pintype "passive"))
    )
    (net (code "154") (name "Y4") (class "Default")
      (node (ref "OR_1") (pin "11") (pinfunction "Y4_11") (pintype "output"))
      (node (ref "R61") (pin "2") (pinfunction "2_2") (pintype "passive"))
    )
    (net (code "155") (name "Y5") (class "Default")
      (node (ref "OR_2") (pin "3") (pinfunction "Y1_3") (pintype "output"))
      (node (ref "R68") (pin "2") (pinfunction "2_2") (pintype "passive"))
    )
    (net (code "156") (name "Y6") (class "Default")
      (node (ref "OR_2") (pin "6") (pinfunction "Y2_6") (pintype "output"))
      (node (ref "R67") (pin "2") (pinfunction "2_2") (pintype "passive"))
    )
    (net (code "157") (name "Y7") (class "Default")
      (node (ref "OR_2") (pin "8") (pinfunction "Y3_8") (pintype "output"))
      (node (ref "R66") (pin "2") (pinfunction "2_2") (pintype "passive"))
    )
    (net (code "158") (name "Y8") (class "Default")
      (node (ref "OR_2") (pin "11") (pinfunction "Y4_11") (pintype "output"))
      (node (ref "R65") (pin "2") (pinfunction "2_2") (pintype "passive"))
    )
    (net (code "159") (name "Y9") (class "Default")
      (node (ref "OR_3") (pin "3") (pinfunction "Y1_3") (pintype "output"))
      (node (ref "R72") (pin "2") (pinfunction "2_2") (pintype "passive"))
    )
    (net (code "160") (name "Y10") (class "Default")
      (node (ref "OR_3") (pin "6") (pinfunction "Y2_6") (pintype "output"))
      (node (ref "R71") (pin "2") (pinfunction "2_2") (pintype "passive"))
    )
    (net (code "161") (name "Y11") (class "Default")
      (node (ref "OR_3") (pin "8") (pinfunction "Y3_8") (pintype "output"))
      (node (ref "R70") (pin "2") (pinfunction "2_2") (pintype "passive"))
    )
    (net (code "162") (name "Y12") (class "Default")
      (node (ref "OR_3") (pin "11") (pinfunction "Y4_11") (pintype "output"))
      (node (ref "R69") (pin "2") (pinfunction "2_2") (pintype "passive"))
    )
    (net (code "163") (name "Y13") (class "Default")
      (node (ref "OR_4") (pin "3") (pinfunction "Y1_3") (pintype "output"))
      (node (ref "R76") (pin "2") (pinfunction "2_2") (pintype "passive"))
    )
    (net (code "164") (name "Y14") (class "Default")
      (node (ref "OR_4") (pin "6") (pinfunction "Y2_6") (pintype "output"))
      (node (ref "R75") (pin "2") (pinfunction "2_2") (pintype "passive"))
    )
    (net (code "165") (name "Y15") (class "Default")
      (node (ref "OR_4") (pin "8") (pinfunction "Y3_8") (pintype "output"))
      (node (ref "R74") (pin "2") (pinfunction "2_2") (pintype "passive"))
    )
    (net (code "166") (name "unconnected-(MAIN_POWER-1-OFF-Pad1)") (class "Default")
      (node (ref "MAIN_POWER") (pin "1") (pinfunction "1-OFF_1") (pintype "passive"))
    )
    (net (code "167") (name "unconnected-(OR_4-A4-Pad12)") (class "Default")
      (node (ref "OR_4") (pin "12") (pinfunction "A4_12") (pintype "input"))
    )
    (net (code "168") (name "unconnected-(OR_4-B4-Pad13)") (class "Default")
      (node (ref "OR_4") (pin "13") (pinfunction "B4_13") (pintype "input"))
    )
    (net (code "169") (name "unconnected-(OR_4-Y4-Pad11)") (class "Default")
      (node (ref "OR_4") (pin "11") (pinfunction "Y4_11") (pintype "output"))
    )
    (net (code "170") (name "unconnected-(OR_6-A4-Pad12)") (class "Default")
      (node (ref "OR_6") (pin "12") (pinfunction "A4_12") (pintype "input"))
    )
    (net (code "171") (name "unconnected-(OR_6-B4-Pad13)") (class "Default")
      (node (ref "OR_6") (pin "13") (pinfunction "B4_13") (pintype "input"))
    )
    (net (code "172") (name "unconnected-(OR_6-Y4-Pad11)") (class "Default")
      (node (ref "OR_6") (pin "11") (pinfunction "Y4_11") (pintype "output"))
    )
  )
)
